# avocado-rev01_ODL.net
KiCad netlist of a schematic drawn in EAGLE
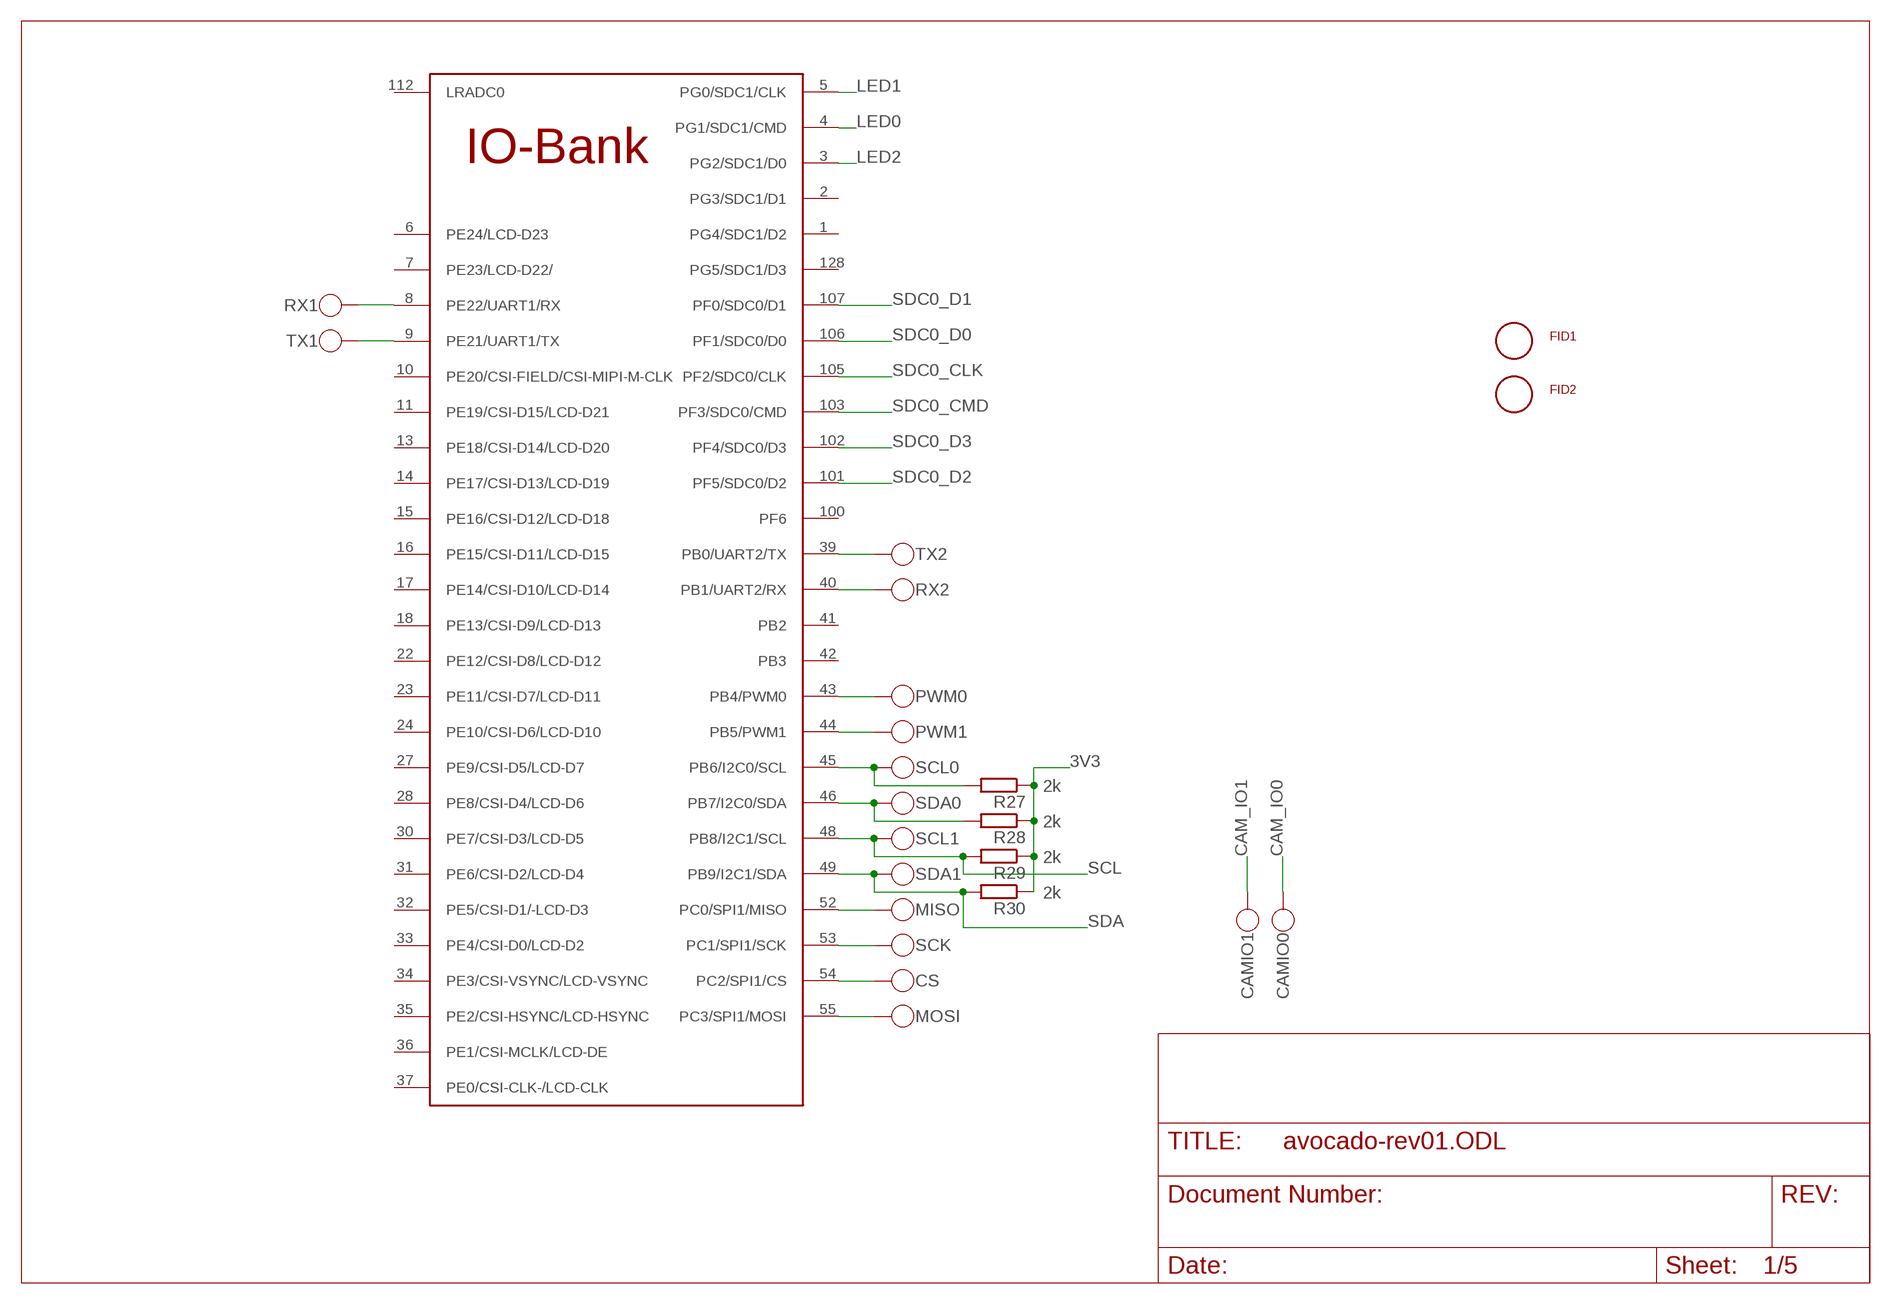
[diagram p0: schematic, sheet 1]
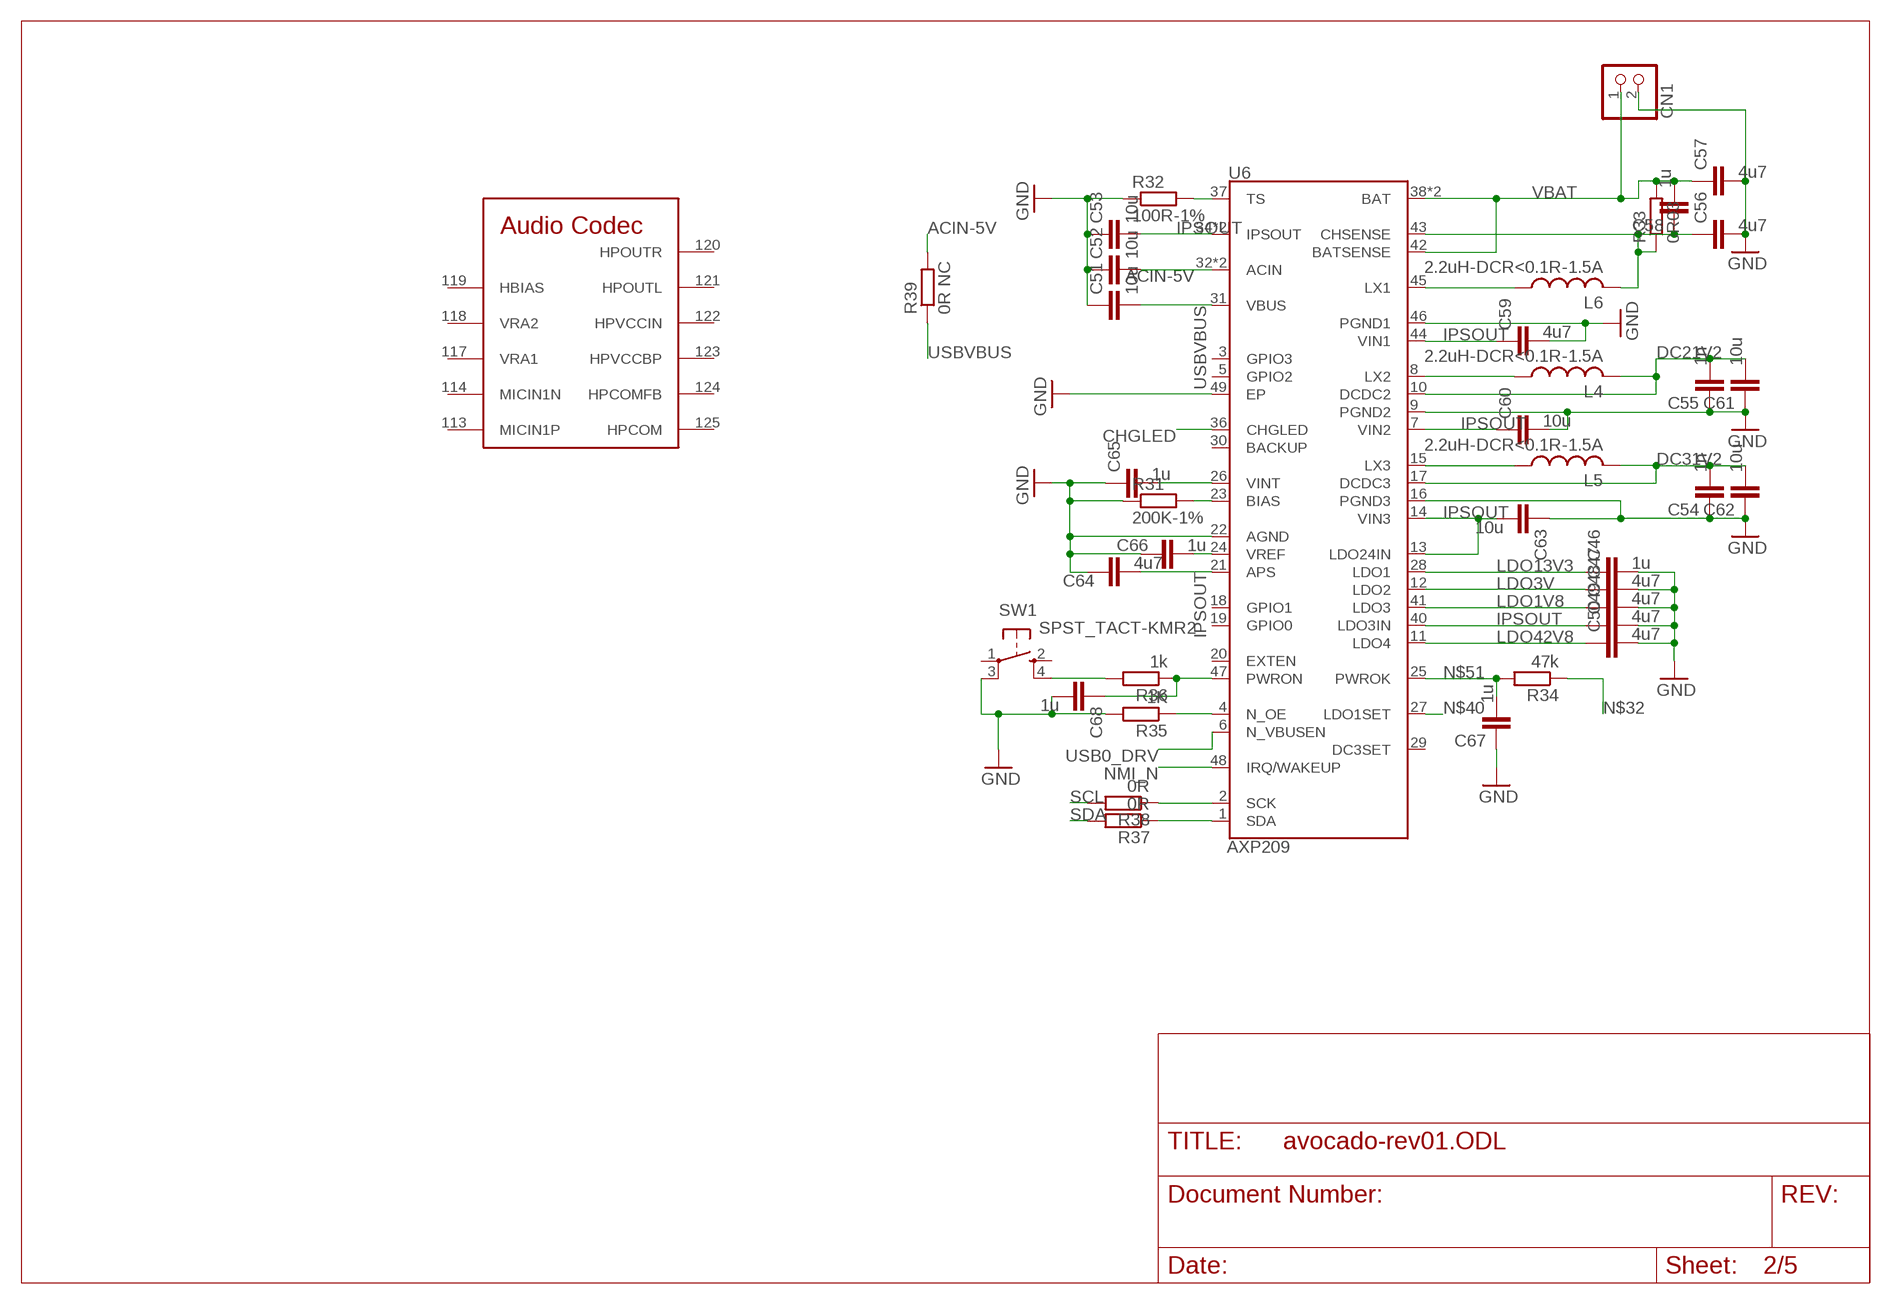
[diagram p1: schematic, sheet 2]
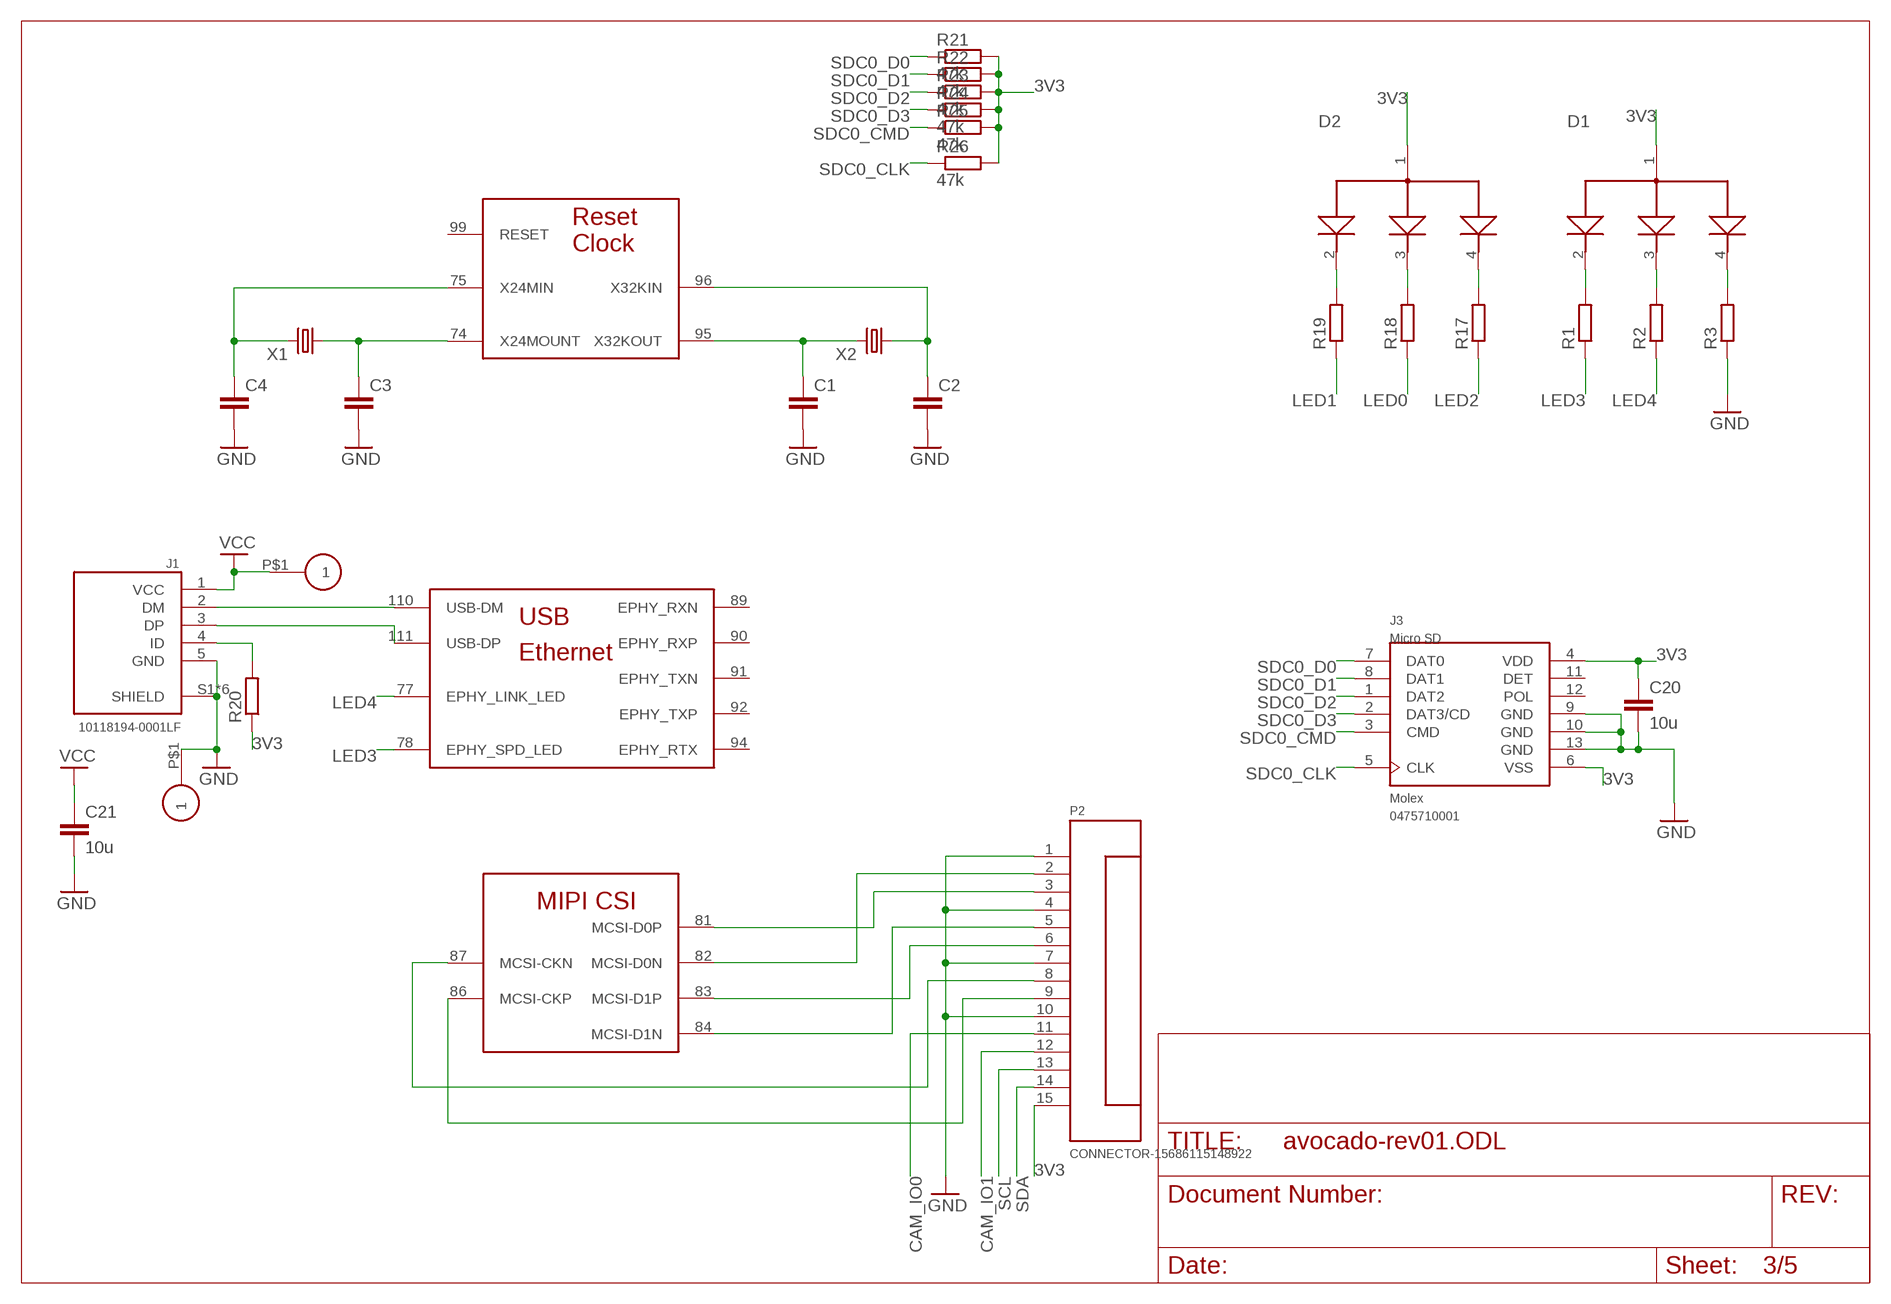
[diagram p2: schematic, sheet 3]
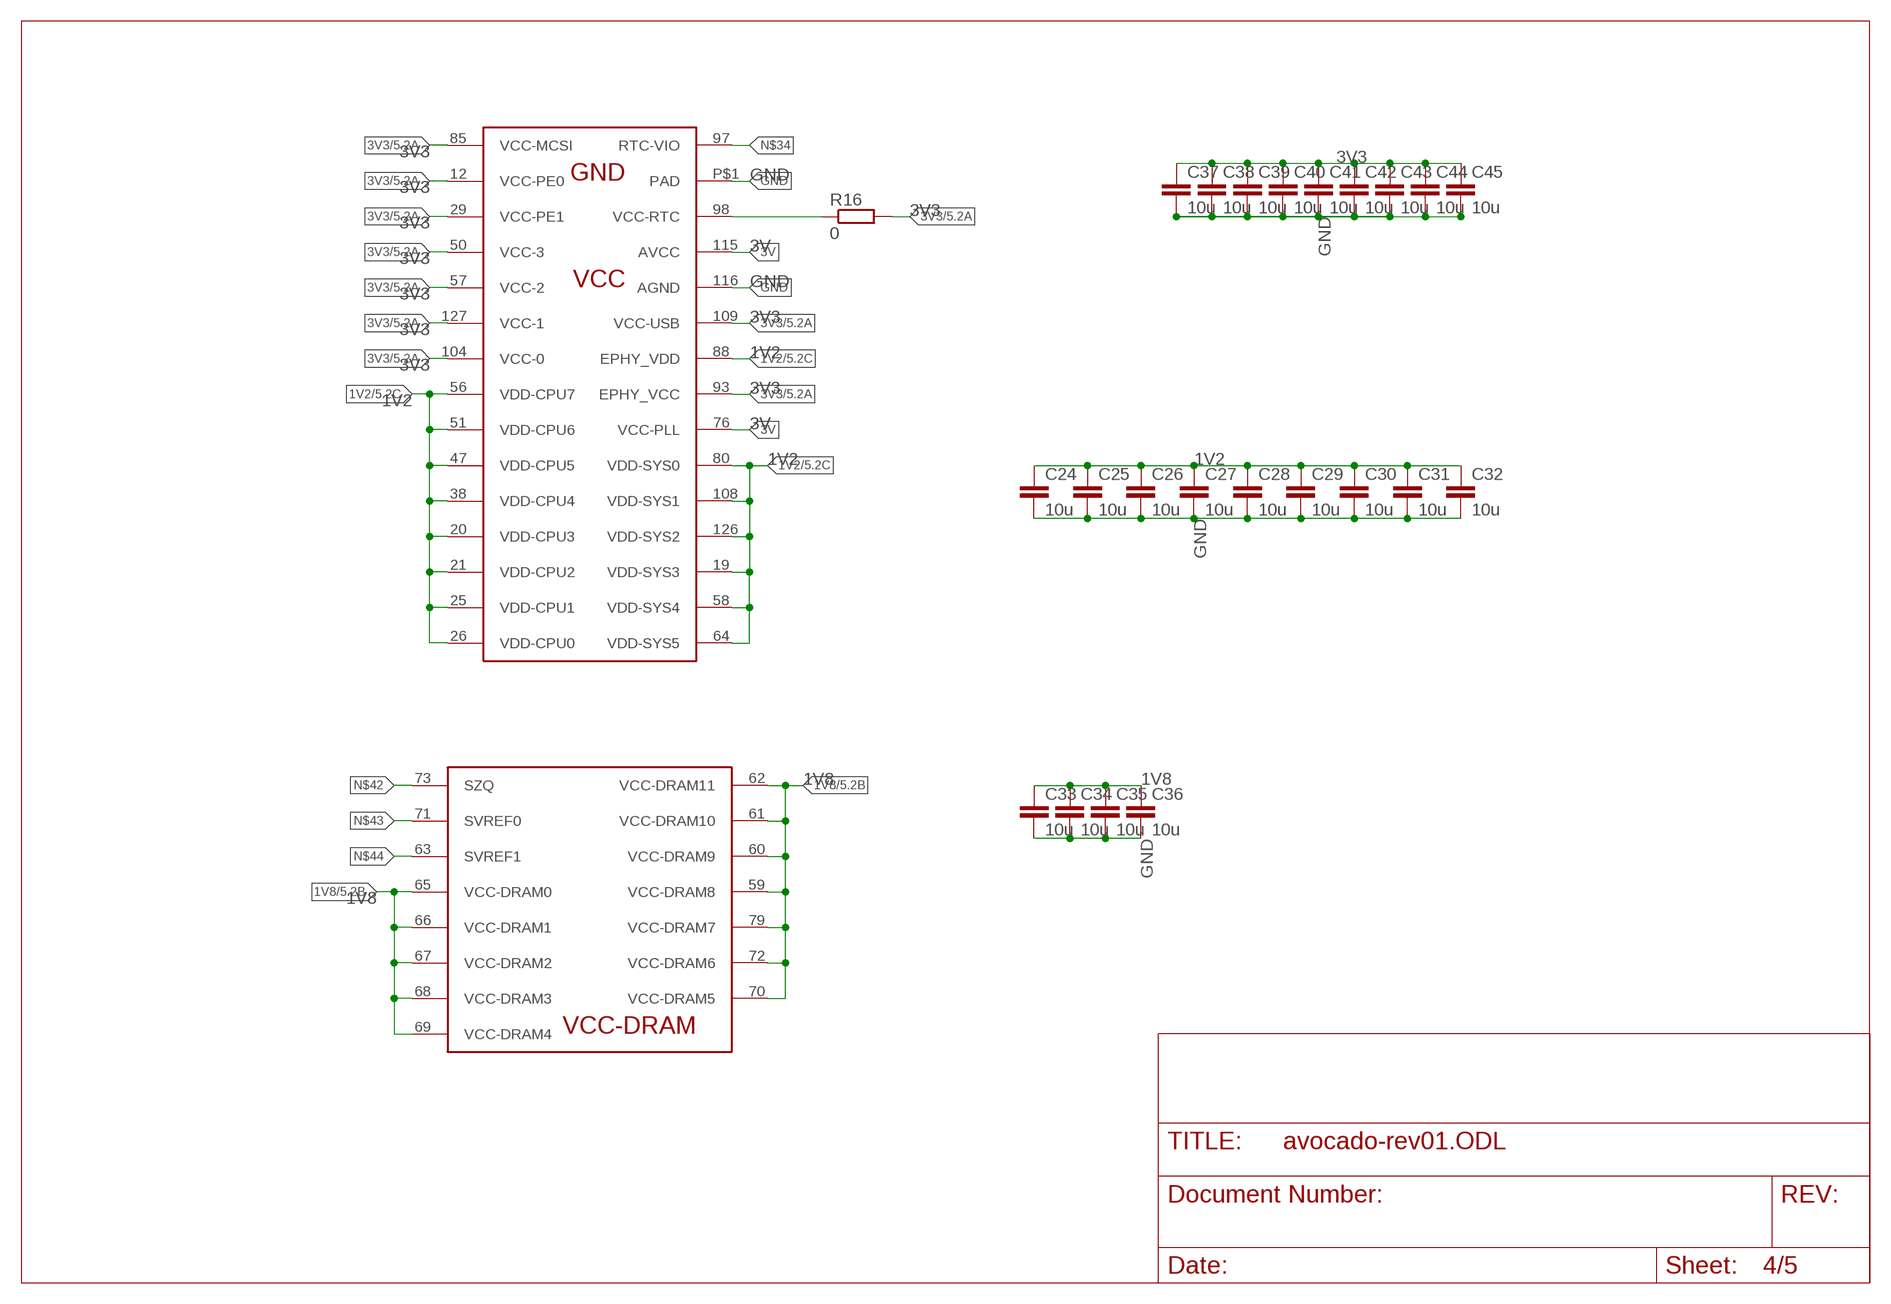
[diagram p3: schematic, sheet 4]
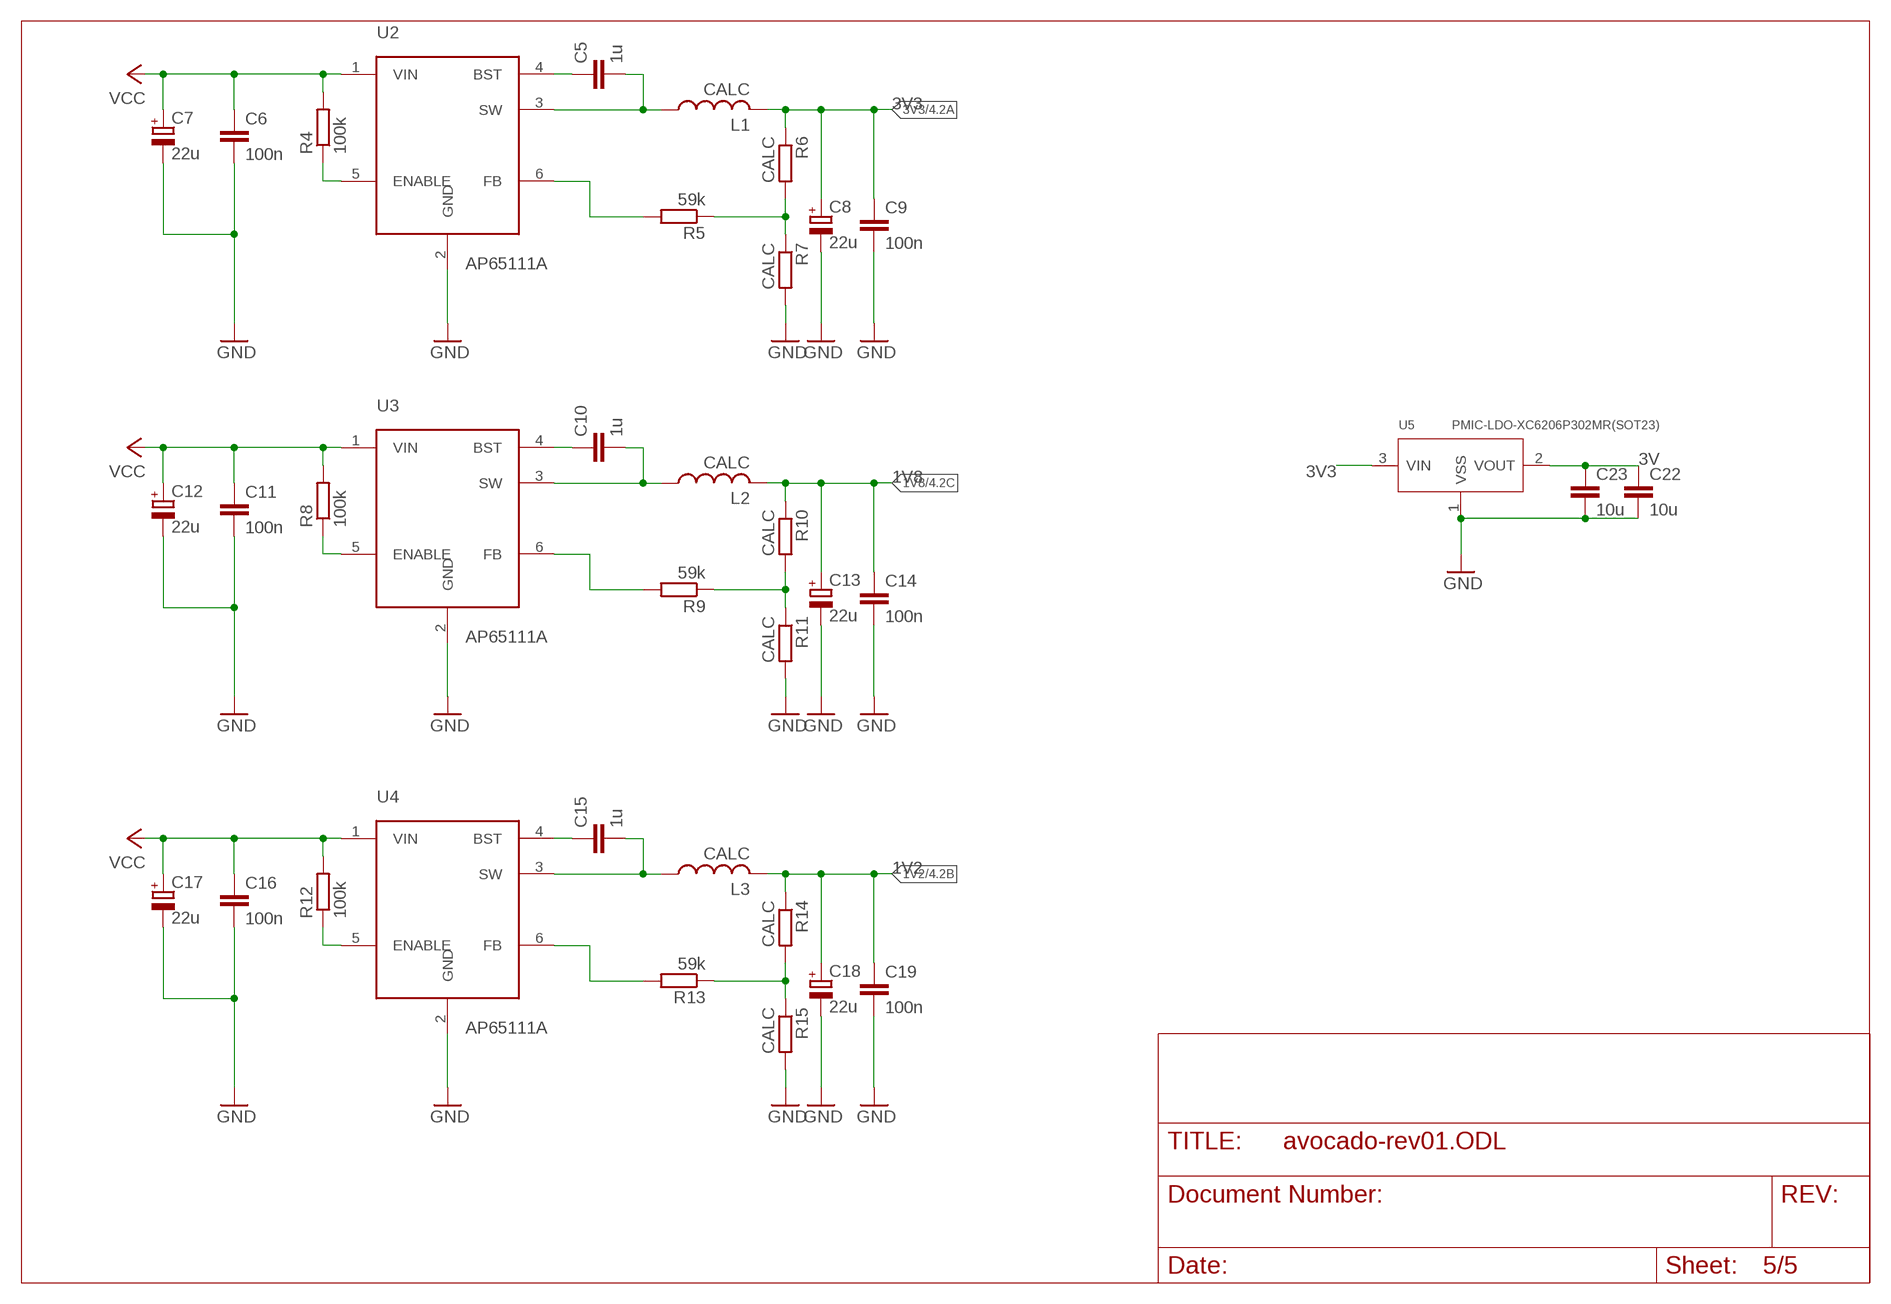
[diagram p4: schematic, sheet 5]

(export (version "E")
  (design (tool "Eeschema 10.0.6"))
  (components
    (comp (ref "C24")
      (value "10u")
      (footprint "eagle-import:C0603")
      (libsource (lib "eagle-import") (part "C0603"))
    )
    (comp (ref "C25")
      (value "10u")
      (footprint "eagle-import:C0603")
      (libsource (lib "eagle-import") (part "C0603"))
    )
    (comp (ref "C26")
      (value "10u")
      (footprint "eagle-import:C0603")
      (libsource (lib "eagle-import") (part "C0603"))
    )
    (comp (ref "C27")
      (value "10u")
      (footprint "eagle-import:C0603")
      (libsource (lib "eagle-import") (part "C0603"))
    )
    (comp (ref "C28")
      (value "10u")
      (footprint "eagle-import:C0603")
      (libsource (lib "eagle-import") (part "C0603"))
    )
    (comp (ref "C29")
      (value "10u")
      (footprint "eagle-import:C0603")
      (libsource (lib "eagle-import") (part "C0603"))
    )
    (comp (ref "C30")
      (value "10u")
      (footprint "eagle-import:C0603")
      (libsource (lib "eagle-import") (part "C0603"))
    )
    (comp (ref "C31")
      (value "10u")
      (footprint "eagle-import:C0603")
      (libsource (lib "eagle-import") (part "C0603"))
    )
    (comp (ref "C32")
      (value "10u")
      (footprint "eagle-import:C0603")
      (libsource (lib "eagle-import") (part "C0603"))
    )
    (comp (ref "C33")
      (value "10u")
      (footprint "eagle-import:C0603")
      (libsource (lib "eagle-import") (part "C0603"))
    )
    (comp (ref "C34")
      (value "10u")
      (footprint "eagle-import:C0603")
      (libsource (lib "eagle-import") (part "C0603"))
    )
    (comp (ref "C35")
      (value "10u")
      (footprint "eagle-import:C0603")
      (libsource (lib "eagle-import") (part "C0603"))
    )
    (comp (ref "C36")
      (value "10u")
      (footprint "eagle-import:C0603")
      (libsource (lib "eagle-import") (part "C0603"))
    )
    (comp (ref "C37")
      (value "10u")
      (footprint "eagle-import:C0603")
      (libsource (lib "eagle-import") (part "C0603"))
    )
    (comp (ref "C38")
      (value "10u")
      (footprint "eagle-import:C0603")
      (libsource (lib "eagle-import") (part "C0603"))
    )
    (comp (ref "C39")
      (value "10u")
      (footprint "eagle-import:C0603")
      (libsource (lib "eagle-import") (part "C0603"))
    )
    (comp (ref "C40")
      (value "10u")
      (footprint "eagle-import:C0603")
      (libsource (lib "eagle-import") (part "C0603"))
    )
    (comp (ref "C41")
      (value "10u")
      (footprint "eagle-import:C0603")
      (libsource (lib "eagle-import") (part "C0603"))
    )
    (comp (ref "C42")
      (value "10u")
      (footprint "eagle-import:C0603")
      (libsource (lib "eagle-import") (part "C0603"))
    )
    (comp (ref "C43")
      (value "10u")
      (footprint "eagle-import:C0603")
      (libsource (lib "eagle-import") (part "C0603"))
    )
    (comp (ref "C44")
      (value "10u")
      (footprint "eagle-import:C0603")
      (libsource (lib "eagle-import") (part "C0603"))
    )
    (comp (ref "C45")
      (value "10u")
      (footprint "eagle-import:C0603")
      (libsource (lib "eagle-import") (part "C0603"))
    )
    (comp (ref "R16")
      (value "0")
      (footprint "eagle-import:R0603")
      (libsource (lib "eagle-import") (part "R0603"))
    )
    (comp (ref "U1")
      (value "V3S")
      (footprint "eagle-import:QFP-128")
      (fields (field (name "MPN") "V3s"))
      (libsource (lib "eagle-import") (part "V3S"))
    )
    (comp (ref "C46")
      (value "1u")
      (footprint "eagle-import:C0603")
      (libsource (lib "eagle-import") (part "C0603"))
    )
    (comp (ref "C47")
      (value "4u7")
      (footprint "eagle-import:C0603")
      (libsource (lib "eagle-import") (part "C0603"))
    )
    (comp (ref "C48")
      (value "4u7")
      (footprint "eagle-import:C0603")
      (libsource (lib "eagle-import") (part "C0603"))
    )
    (comp (ref "C49")
      (value "4u7")
      (footprint "eagle-import:C0603")
      (libsource (lib "eagle-import") (part "C0603"))
    )
    (comp (ref "C50")
      (value "4u7")
      (footprint "eagle-import:C0603")
      (libsource (lib "eagle-import") (part "C0603"))
    )
    (comp (ref "C51")
      (value "10u")
      (footprint "eagle-import:C0603")
      (libsource (lib "eagle-import") (part "C0603"))
    )
    (comp (ref "C52")
      (value "10u")
      (footprint "eagle-import:C0603")
      (libsource (lib "eagle-import") (part "C0603"))
    )
    (comp (ref "C53")
      (value "10u")
      (footprint "eagle-import:C0603")
      (libsource (lib "eagle-import") (part "C0603"))
    )
    (comp (ref "C54")
      (value "1n")
      (footprint "eagle-import:C0603")
      (libsource (lib "eagle-import") (part "C0603"))
    )
    (comp (ref "C55")
      (value "1n")
      (footprint "eagle-import:C0603")
      (libsource (lib "eagle-import") (part "C0603"))
    )
    (comp (ref "C56")
      (value "4u7")
      (footprint "eagle-import:C0603")
      (libsource (lib "eagle-import") (part "C0603"))
    )
    (comp (ref "C57")
      (value "4u7")
      (footprint "eagle-import:C0603")
      (libsource (lib "eagle-import") (part "C0603"))
    )
    (comp (ref "C58")
      (value "1u")
      (footprint "eagle-import:C0603")
      (libsource (lib "eagle-import") (part "C0603"))
    )
    (comp (ref "C59")
      (value "4u7")
      (footprint "eagle-import:C0603")
      (libsource (lib "eagle-import") (part "C0603"))
    )
    (comp (ref "C60")
      (value "10u")
      (footprint "eagle-import:C0603")
      (libsource (lib "eagle-import") (part "C0603"))
    )
    (comp (ref "C61")
      (value "10u")
      (footprint "eagle-import:C0603")
      (libsource (lib "eagle-import") (part "C0603"))
    )
    (comp (ref "C62")
      (value "10u")
      (footprint "eagle-import:C0603")
      (libsource (lib "eagle-import") (part "C0603"))
    )
    (comp (ref "C63")
      (value "10u")
      (footprint "eagle-import:C0603")
      (libsource (lib "eagle-import") (part "C0603"))
    )
    (comp (ref "C64")
      (value "4u7")
      (footprint "eagle-import:C0603")
      (libsource (lib "eagle-import") (part "C0603"))
    )
    (comp (ref "C65")
      (value "1u")
      (footprint "eagle-import:C0603")
      (libsource (lib "eagle-import") (part "C0603"))
    )
    (comp (ref "C66")
      (value "1u")
      (footprint "eagle-import:C0603")
      (libsource (lib "eagle-import") (part "C0603"))
    )
    (comp (ref "C67")
      (value "1u")
      (footprint "eagle-import:C0603")
      (libsource (lib "eagle-import") (part "C0603"))
    )
    (comp (ref "C68")
      (value "1u")
      (footprint "eagle-import:C0603")
      (libsource (lib "eagle-import") (part "C0603"))
    )
    (comp (ref "CN1")
      (value "JST_2PIN-SMT-RA")
      (footprint "eagle-import:JST-PH-2-SMT-RA")
      (libsource (lib "eagle-import") (part "JST_2PIN-SMT-RA"))
    )
    (comp (ref "L4")
      (value "2.2uH-DCR<0.1R-1.5A")
      (footprint "eagle-import:B82462A4153K")
      (fields (field (name "MPN") "B82462A4153K"))
      (libsource (lib "eagle-import") (part "L6X6"))
    )
    (comp (ref "L5")
      (value "2.2uH-DCR<0.1R-1.5A")
      (footprint "eagle-import:B82462A4153K")
      (fields (field (name "MPN") "B82462A4153K"))
      (libsource (lib "eagle-import") (part "L6X6"))
    )
    (comp (ref "L6")
      (value "2.2uH-DCR<0.1R-1.5A")
      (footprint "eagle-import:B82462A4153K")
      (fields (field (name "MPN") "B82462A4153K"))
      (libsource (lib "eagle-import") (part "L6X6"))
    )
    (comp (ref "R31")
      (value "200K-1%")
      (footprint "eagle-import:R0402")
      (libsource (lib "eagle-import") (part "R-EU_R0402"))
    )
    (comp (ref "R32")
      (value "100R-1%")
      (footprint "eagle-import:R0402")
      (libsource (lib "eagle-import") (part "R-EU_R0402"))
    )
    (comp (ref "R33")
      (value "0R03")
      (footprint "eagle-import:R1206")
      (libsource (lib "eagle-import") (part "R-EU_R1206"))
    )
    (comp (ref "R34")
      (value "47k")
      (footprint "eagle-import:R0402")
      (libsource (lib "eagle-import") (part "R-EU_R0402"))
    )
    (comp (ref "R35")
      (value "1K")
      (footprint "eagle-import:R0402")
      (libsource (lib "eagle-import") (part "R-EU_R0402"))
    )
    (comp (ref "R36")
      (value "1k")
      (footprint "eagle-import:R0402")
      (libsource (lib "eagle-import") (part "R-EU_R0402"))
    )
    (comp (ref "R37")
      (value "0R")
      (footprint "eagle-import:R0402")
      (libsource (lib "eagle-import") (part "R-EU_R0402"))
    )
    (comp (ref "R38")
      (value "0R")
      (footprint "eagle-import:R0402")
      (libsource (lib "eagle-import") (part "R-EU_R0402"))
    )
    (comp (ref "R39")
      (value "0R NC")
      (footprint "eagle-import:R0402")
      (libsource (lib "eagle-import") (part "R-EU_R0402"))
    )
    (comp (ref "SW1")
      (value "SPST_TACT-KMR2")
      (footprint "eagle-import:KMR2")
      (libsource (lib "eagle-import") (part "SPST_TACT-KMR2"))
    )
    (comp (ref "U6")
      (value "AXP209")
      (footprint "eagle-import:QFN40P600X600X80-49N")
      (description "IC")
      (fields (field (name "MF") "X-Powers Limited"))
      (libsource (lib "eagle-import") (part "AXP209"))
    )
    (comp (ref "CAMIO0")
      (value "TEST_TESTPOINT")
      (footprint "eagle-import:TEST_TESTPOINT")
      (libsource (lib "eagle-import") (part "TEST_TESTPOINT"))
    )
    (comp (ref "CAMIO1")
      (value "TEST_TESTPOINT")
      (footprint "eagle-import:TEST_TESTPOINT")
      (libsource (lib "eagle-import") (part "TEST_TESTPOINT"))
    )
    (comp (ref "CS")
      (value "TEST_TESTPOINT")
      (footprint "eagle-import:TEST_TESTPOINT")
      (libsource (lib "eagle-import") (part "TEST_TESTPOINT"))
    )
    (comp (ref "FID1")
      (value "FIDUCIAL")
      (footprint "eagle-import:FIDUCIAL_1MM")
      (libsource (lib "eagle-import") (part "FIDUCIAL"))
    )
    (comp (ref "FID2")
      (value "FIDUCIAL")
      (footprint "eagle-import:FIDUCIAL_1MM")
      (libsource (lib "eagle-import") (part "FIDUCIAL"))
    )
    (comp (ref "MISO")
      (value "TEST_TESTPOINT")
      (footprint "eagle-import:TEST_TESTPOINT")
      (libsource (lib "eagle-import") (part "TEST_TESTPOINT"))
    )
    (comp (ref "MOSI")
      (value "TEST_TESTPOINT")
      (footprint "eagle-import:TEST_TESTPOINT")
      (libsource (lib "eagle-import") (part "TEST_TESTPOINT"))
    )
    (comp (ref "PWM0")
      (value "TEST_TESTPOINT")
      (footprint "eagle-import:TEST_TESTPOINT")
      (libsource (lib "eagle-import") (part "TEST_TESTPOINT"))
    )
    (comp (ref "PWM1")
      (value "TEST_TESTPOINT")
      (footprint "eagle-import:TEST_TESTPOINT")
      (libsource (lib "eagle-import") (part "TEST_TESTPOINT"))
    )
    (comp (ref "R27")
      (value "2k")
      (footprint "eagle-import:R0603")
      (libsource (lib "eagle-import") (part "R-EU_R0603"))
    )
    (comp (ref "R28")
      (value "2k")
      (footprint "eagle-import:R0603")
      (libsource (lib "eagle-import") (part "R-EU_R0603"))
    )
    (comp (ref "R29")
      (value "2k")
      (footprint "eagle-import:R0603")
      (libsource (lib "eagle-import") (part "R-EU_R0603"))
    )
    (comp (ref "R30")
      (value "2k")
      (footprint "eagle-import:R0603")
      (libsource (lib "eagle-import") (part "R-EU_R0603"))
    )
    (comp (ref "RX1")
      (value "TEST_TESTPOINT")
      (footprint "eagle-import:TEST_TESTPOINT")
      (libsource (lib "eagle-import") (part "TEST_TESTPOINT"))
    )
    (comp (ref "RX2")
      (value "TEST_TESTPOINT")
      (footprint "eagle-import:TEST_TESTPOINT")
      (libsource (lib "eagle-import") (part "TEST_TESTPOINT"))
    )
    (comp (ref "SCK")
      (value "TEST_TESTPOINT")
      (footprint "eagle-import:TEST_TESTPOINT")
      (libsource (lib "eagle-import") (part "TEST_TESTPOINT"))
    )
    (comp (ref "SCL0")
      (value "TEST_TESTPOINT")
      (footprint "eagle-import:TEST_TESTPOINT")
      (libsource (lib "eagle-import") (part "TEST_TESTPOINT"))
    )
    (comp (ref "SCL1")
      (value "TEST_TESTPOINT")
      (footprint "eagle-import:TEST_TESTPOINT")
      (libsource (lib "eagle-import") (part "TEST_TESTPOINT"))
    )
    (comp (ref "SDA0")
      (value "TEST_TESTPOINT")
      (footprint "eagle-import:TEST_TESTPOINT")
      (libsource (lib "eagle-import") (part "TEST_TESTPOINT"))
    )
    (comp (ref "SDA1")
      (value "TEST_TESTPOINT")
      (footprint "eagle-import:TEST_TESTPOINT")
      (libsource (lib "eagle-import") (part "TEST_TESTPOINT"))
    )
    (comp (ref "TX1")
      (value "TEST_TESTPOINT")
      (footprint "eagle-import:TEST_TESTPOINT")
      (libsource (lib "eagle-import") (part "TEST_TESTPOINT"))
    )
    (comp (ref "TX2")
      (value "TEST_TESTPOINT")
      (footprint "eagle-import:TEST_TESTPOINT")
      (libsource (lib "eagle-import") (part "TEST_TESTPOINT"))
    )
    (comp (ref "5V")
      (value "PADTH")
      (footprint "eagle-import:PAD")
      (libsource (lib "eagle-import") (part "PADTH"))
    )
    (comp (ref "C1")
      (value "C0603")
      (footprint "eagle-import:C0603")
      (libsource (lib "eagle-import") (part "C0603"))
    )
    (comp (ref "C2")
      (value "C0603")
      (footprint "eagle-import:C0603")
      (libsource (lib "eagle-import") (part "C0603"))
    )
    (comp (ref "C3")
      (value "C0603")
      (footprint "eagle-import:C0603")
      (libsource (lib "eagle-import") (part "C0603"))
    )
    (comp (ref "C4")
      (value "C0603")
      (footprint "eagle-import:C0603")
      (libsource (lib "eagle-import") (part "C0603"))
    )
    (comp (ref "C20")
      (value "10u")
      (footprint "eagle-import:C0603")
      (libsource (lib "eagle-import") (part "C0603"))
    )
    (comp (ref "C21")
      (value "10u")
      (footprint "eagle-import:C0603")
      (libsource (lib "eagle-import") (part "C0603"))
    )
    (comp (ref "D1")
      (value "LL-R3528RGBC-008-B")
      (footprint "eagle-import:LED_LL-R3528RGBC-008-B")
      (fields (field (name "MF") "Lucky Light"))
      (libsource (lib "eagle-import") (part "LL-R3528RGBC-008-B"))
    )
    (comp (ref "D2")
      (value "LL-R3528RGBC-008-B")
      (footprint "eagle-import:LED_LL-R3528RGBC-008-B")
      (fields (field (name "MF") "Lucky Light"))
      (libsource (lib "eagle-import") (part "LL-R3528RGBC-008-B"))
    )
    (comp (ref "GND")
      (value "PADTH")
      (footprint "eagle-import:PAD")
      (libsource (lib "eagle-import") (part "PADTH"))
    )
    (comp (ref "J1")
      (value "10118194-0001LF")
      (footprint "eagle-import:AMPHENOL_10118194-0001LF")
      (fields (field (name "MF") "Amphenol ICC"))
      (libsource (lib "eagle-import") (part "10118194-0001LF"))
    )
    (comp (ref "J3")
      (value "0475710001")
      (footprint "eagle-import:MOLEX_0475710001")
      (fields (field (name "MF") "Molex"))
      (libsource (lib "eagle-import") (part "0475710001"))
    )
    (comp (ref "P2")
      (value "CONNECTOR-15686115148922")
      (footprint "eagle-import:686115148922")
      (fields (field (name "MPN") "686115148922"))
      (libsource (lib "eagle-import") (part "CONNECTOR-15686115148922"))
    )
    (comp (ref "R1")
      (value "R-EU_R0603")
      (footprint "eagle-import:R0603")
      (libsource (lib "eagle-import") (part "R-EU_R0603"))
    )
    (comp (ref "R2")
      (value "R-EU_R0603")
      (footprint "eagle-import:R0603")
      (libsource (lib "eagle-import") (part "R-EU_R0603"))
    )
    (comp (ref "R3")
      (value "R-EU_R0603")
      (footprint "eagle-import:R0603")
      (libsource (lib "eagle-import") (part "R-EU_R0603"))
    )
    (comp (ref "R17")
      (value "R-EU_R0603")
      (footprint "eagle-import:R0603")
      (libsource (lib "eagle-import") (part "R-EU_R0603"))
    )
    (comp (ref "R18")
      (value "R-EU_R0603")
      (footprint "eagle-import:R0603")
      (libsource (lib "eagle-import") (part "R-EU_R0603"))
    )
    (comp (ref "R19")
      (value "R-EU_R0603")
      (footprint "eagle-import:R0603")
      (libsource (lib "eagle-import") (part "R-EU_R0603"))
    )
    (comp (ref "R20")
      (value "R-EU_R0603")
      (footprint "eagle-import:R0603")
      (libsource (lib "eagle-import") (part "R-EU_R0603"))
    )
    (comp (ref "R21")
      (value "47k")
      (footprint "eagle-import:R0603")
      (libsource (lib "eagle-import") (part "R-EU_R0603"))
    )
    (comp (ref "R22")
      (value "47k")
      (footprint "eagle-import:R0603")
      (libsource (lib "eagle-import") (part "R-EU_R0603"))
    )
    (comp (ref "R23")
      (value "47k")
      (footprint "eagle-import:R0603")
      (libsource (lib "eagle-import") (part "R-EU_R0603"))
    )
    (comp (ref "R24")
      (value "47k")
      (footprint "eagle-import:R0603")
      (libsource (lib "eagle-import") (part "R-EU_R0603"))
    )
    (comp (ref "R25")
      (value "47k")
      (footprint "eagle-import:R0603")
      (libsource (lib "eagle-import") (part "R-EU_R0603"))
    )
    (comp (ref "R26")
      (value "47k")
      (footprint "eagle-import:R0603")
      (libsource (lib "eagle-import") (part "R-EU_R0603"))
    )
    (comp (ref "X1")
      (value "XTAL3.2X2")
      (footprint "eagle-import:3.2X2-4")
      (libsource (lib "eagle-import") (part "XTAL3.2X2"))
    )
    (comp (ref "X2")
      (value "XTAL5X1.9")
      (footprint "eagle-import:XTAL-5X1.9")
      (libsource (lib "eagle-import") (part "XTAL5X1.9"))
    )
    (comp (ref "C5")
      (value "1u")
      (footprint "eagle-import:C0603")
      (libsource (lib "eagle-import") (part "C0603"))
    )
    (comp (ref "C6")
      (value "100n")
      (footprint "eagle-import:C0603")
      (libsource (lib "eagle-import") (part "C0603"))
    )
    (comp (ref "C7")
      (value "22u")
      (footprint "eagle-import:CAP4.3X6.1")
      (libsource (lib "eagle-import") (part "C_POL4.3"))
    )
    (comp (ref "C8")
      (value "22u")
      (footprint "eagle-import:CAP4.3X6.1")
      (libsource (lib "eagle-import") (part "C_POL4.3"))
    )
    (comp (ref "C9")
      (value "100n")
      (footprint "eagle-import:C0603")
      (libsource (lib "eagle-import") (part "C0603"))
    )
    (comp (ref "C10")
      (value "1u")
      (footprint "eagle-import:C0603")
      (libsource (lib "eagle-import") (part "C0603"))
    )
    (comp (ref "C11")
      (value "100n")
      (footprint "eagle-import:C0603")
      (libsource (lib "eagle-import") (part "C0603"))
    )
    (comp (ref "C12")
      (value "22u")
      (footprint "eagle-import:CAP4.3X6.1")
      (libsource (lib "eagle-import") (part "C_POL4.3"))
    )
    (comp (ref "C13")
      (value "22u")
      (footprint "eagle-import:CAP4.3X6.1")
      (libsource (lib "eagle-import") (part "C_POL4.3"))
    )
    (comp (ref "C14")
      (value "100n")
      (footprint "eagle-import:C0603")
      (libsource (lib "eagle-import") (part "C0603"))
    )
    (comp (ref "C15")
      (value "1u")
      (footprint "eagle-import:C0603")
      (libsource (lib "eagle-import") (part "C0603"))
    )
    (comp (ref "C16")
      (value "100n")
      (footprint "eagle-import:C0603")
      (libsource (lib "eagle-import") (part "C0603"))
    )
    (comp (ref "C17")
      (value "22u")
      (footprint "eagle-import:CAP4.3X6.1")
      (libsource (lib "eagle-import") (part "C_POL4.3"))
    )
    (comp (ref "C18")
      (value "22u")
      (footprint "eagle-import:CAP4.3X6.1")
      (libsource (lib "eagle-import") (part "C_POL4.3"))
    )
    (comp (ref "C19")
      (value "100n")
      (footprint "eagle-import:C0603")
      (libsource (lib "eagle-import") (part "C0603"))
    )
    (comp (ref "C22")
      (value "10u")
      (footprint "eagle-import:C0603")
      (libsource (lib "eagle-import") (part "C0603"))
    )
    (comp (ref "C23")
      (value "10u")
      (footprint "eagle-import:C0603")
      (libsource (lib "eagle-import") (part "C0603"))
    )
    (comp (ref "L1")
      (value "CALC")
      (footprint "eagle-import:B82462A4153K")
      (fields (field (name "MPN") "B82462A4153K"))
      (libsource (lib "eagle-import") (part "L6X6"))
    )
    (comp (ref "L2")
      (value "CALC")
      (footprint "eagle-import:B82462A4153K")
      (fields (field (name "MPN") "B82462A4153K"))
      (libsource (lib "eagle-import") (part "L6X6"))
    )
    (comp (ref "L3")
      (value "CALC")
      (footprint "eagle-import:B82462A4153K")
      (fields (field (name "MPN") "B82462A4153K"))
      (libsource (lib "eagle-import") (part "L6X6"))
    )
    (comp (ref "R4")
      (value "100k")
      (footprint "eagle-import:R0603")
      (libsource (lib "eagle-import") (part "R0603"))
    )
    (comp (ref "R5")
      (value "59k")
      (footprint "eagle-import:R0603")
      (libsource (lib "eagle-import") (part "R0603"))
    )
    (comp (ref "R6")
      (value "CALC")
      (footprint "eagle-import:R0603")
      (libsource (lib "eagle-import") (part "R0603"))
    )
    (comp (ref "R7")
      (value "CALC")
      (footprint "eagle-import:R0603")
      (libsource (lib "eagle-import") (part "R0603"))
    )
    (comp (ref "R8")
      (value "100k")
      (footprint "eagle-import:R0603")
      (libsource (lib "eagle-import") (part "R0603"))
    )
    (comp (ref "R9")
      (value "59k")
      (footprint "eagle-import:R0603")
      (libsource (lib "eagle-import") (part "R0603"))
    )
    (comp (ref "R10")
      (value "CALC")
      (footprint "eagle-import:R0603")
      (libsource (lib "eagle-import") (part "R0603"))
    )
    (comp (ref "R11")
      (value "CALC")
      (footprint "eagle-import:R0603")
      (libsource (lib "eagle-import") (part "R0603"))
    )
    (comp (ref "R12")
      (value "100k")
      (footprint "eagle-import:R0603")
      (libsource (lib "eagle-import") (part "R0603"))
    )
    (comp (ref "R13")
      (value "59k")
      (footprint "eagle-import:R0603")
      (libsource (lib "eagle-import") (part "R0603"))
    )
    (comp (ref "R14")
      (value "CALC")
      (footprint "eagle-import:R0603")
      (libsource (lib "eagle-import") (part "R0603"))
    )
    (comp (ref "R15")
      (value "CALC")
      (footprint "eagle-import:R0603")
      (libsource (lib "eagle-import") (part "R0603"))
    )
    (comp (ref "U2")
      (value "AP65111A")
      (footprint "eagle-import:TSOT26")
      (fields (field (name "MPN") "AP65111AWU-7"))
      (libsource (lib "eagle-import") (part "AP65111A"))
    )
    (comp (ref "U3")
      (value "AP65111A")
      (footprint "eagle-import:TSOT26")
      (fields (field (name "MPN") "AP65111AWU-7"))
      (libsource (lib "eagle-import") (part "AP65111A"))
    )
    (comp (ref "U4")
      (value "AP65111A")
      (footprint "eagle-import:TSOT26")
      (fields (field (name "MPN") "AP65111AWU-7"))
      (libsource (lib "eagle-import") (part "AP65111A"))
    )
    (comp (ref "U5")
      (value "PMIC-LDO-XC6206P302MR(SOT23)")
      (footprint "eagle-import:SOT-23")
      (description "N/A")
      (fields
        (field (name "MF") "Torex")
        (field (name "MP") "XC6206P302MR")
        (field (name "AVAILABILITY") "N/A")
      )
      (libsource (lib "eagle-import") (part "PMIC-LDO-XC6206P302MR(SOT23)"))
    )
  )
  (nets
    (net (code "1") (name "1V2") (class "Default")
      (node (ref "C18") (pin "1") (pinfunction "+_1") (pintype "passive"))
      (node (ref "C19") (pin "1") (pinfunction "1_1") (pintype "passive"))
      (node (ref "C24") (pin "1") (pinfunction "1_1") (pintype "passive"))
      (node (ref "C25") (pin "1") (pinfunction "1_1") (pintype "passive"))
      (node (ref "C26") (pin "1") (pinfunction "1_1") (pintype "passive"))
      (node (ref "C27") (pin "1") (pinfunction "1_1") (pintype "passive"))
      (node (ref "C28") (pin "1") (pinfunction "1_1") (pintype "passive"))
      (node (ref "C29") (pin "1") (pinfunction "1_1") (pintype "passive"))
      (node (ref "C30") (pin "1") (pinfunction "1_1") (pintype "passive"))
      (node (ref "C31") (pin "1") (pinfunction "1_1") (pintype "passive"))
      (node (ref "C32") (pin "1") (pinfunction "1_1") (pintype "passive"))
      (node (ref "L3") (pin "P$2") (pinfunction "2_P$2") (pintype "passive"))
      (node (ref "R14") (pin "1") (pinfunction "1_1") (pintype "passive"))
      (node (ref "U1") (pin "108") (pinfunction "VDD-SYS1_108") (pintype "bidirectional"))
      (node (ref "U1") (pin "126") (pinfunction "VDD-SYS2_126") (pintype "bidirectional"))
      (node (ref "U1") (pin "19") (pinfunction "VDD-SYS3_19") (pintype "bidirectional"))
      (node (ref "U1") (pin "20") (pinfunction "VDD-CPU3_20") (pintype "bidirectional"))
      (node (ref "U1") (pin "21") (pinfunction "VDD-CPU2_21") (pintype "bidirectional"))
      (node (ref "U1") (pin "25") (pinfunction "VDD-CPU1_25") (pintype "bidirectional"))
      (node (ref "U1") (pin "26") (pinfunction "VDD-CPU0_26") (pintype "bidirectional"))
      (node (ref "U1") (pin "38") (pinfunction "VDD-CPU4_38") (pintype "bidirectional"))
      (node (ref "U1") (pin "47") (pinfunction "VDD-CPU5_47") (pintype "bidirectional"))
      (node (ref "U1") (pin "51") (pinfunction "VDD-CPU6_51") (pintype "bidirectional"))
      (node (ref "U1") (pin "56") (pinfunction "VDD-CPU7_56") (pintype "bidirectional"))
      (node (ref "U1") (pin "58") (pinfunction "VDD-SYS4_58") (pintype "bidirectional"))
      (node (ref "U1") (pin "64") (pinfunction "VDD-SYS5_64") (pintype "bidirectional"))
      (node (ref "U1") (pin "80") (pinfunction "VDD-SYS0_80") (pintype "bidirectional"))
      (node (ref "U1") (pin "88") (pinfunction "EPHY_VDD_88") (pintype "bidirectional"))
    )
    (net (code "2") (name "1V8") (class "Default")
      (node (ref "C13") (pin "1") (pinfunction "+_1") (pintype "passive"))
      (node (ref "C14") (pin "1") (pinfunction "1_1") (pintype "passive"))
      (node (ref "C33") (pin "1") (pinfunction "1_1") (pintype "passive"))
      (node (ref "C34") (pin "1") (pinfunction "1_1") (pintype "passive"))
      (node (ref "C35") (pin "1") (pinfunction "1_1") (pintype "passive"))
      (node (ref "C36") (pin "1") (pinfunction "1_1") (pintype "passive"))
      (node (ref "L2") (pin "P$2") (pinfunction "2_P$2") (pintype "passive"))
      (node (ref "R10") (pin "1") (pinfunction "1_1") (pintype "passive"))
      (node (ref "U1") (pin "59") (pinfunction "VCC-DRAM8_59") (pintype "bidirectional"))
      (node (ref "U1") (pin "60") (pinfunction "VCC-DRAM9_60") (pintype "bidirectional"))
      (node (ref "U1") (pin "61") (pinfunction "VCC-DRAM10_61") (pintype "bidirectional"))
      (node (ref "U1") (pin "62") (pinfunction "VCC-DRAM11_62") (pintype "bidirectional"))
      (node (ref "U1") (pin "65") (pinfunction "VCC-DRAM0_65") (pintype "bidirectional"))
      (node (ref "U1") (pin "66") (pinfunction "VCC-DRAM1_66") (pintype "bidirectional"))
      (node (ref "U1") (pin "67") (pinfunction "VCC-DRAM2_67") (pintype "bidirectional"))
      (node (ref "U1") (pin "68") (pinfunction "VCC-DRAM3_68") (pintype "bidirectional"))
      (node (ref "U1") (pin "69") (pinfunction "VCC-DRAM4_69") (pintype "bidirectional"))
      (node (ref "U1") (pin "70") (pinfunction "VCC-DRAM5_70") (pintype "bidirectional"))
      (node (ref "U1") (pin "72") (pinfunction "VCC-DRAM6_72") (pintype "bidirectional"))
      (node (ref "U1") (pin "79") (pinfunction "VCC-DRAM7_79") (pintype "bidirectional"))
    )
    (net (code "3") (name "3V") (class "Default")
      (node (ref "C22") (pin "1") (pinfunction "1_1") (pintype "passive"))
      (node (ref "C23") (pin "1") (pinfunction "1_1") (pintype "passive"))
      (node (ref "U1") (pin "115") (pinfunction "AVCC_115") (pintype "bidirectional"))
      (node (ref "U1") (pin "76") (pinfunction "VCC-PLL_76") (pintype "bidirectional"))
      (node (ref "U5") (pin "2") (pinfunction "VOUT_2") (pintype "output"))
    )
    (net (code "4") (name "3V3") (class "Default")
      (node (ref "C20") (pin "1") (pinfunction "1_1") (pintype "passive"))
      (node (ref "C37") (pin "1") (pinfunction "1_1") (pintype "passive"))
      (node (ref "C38") (pin "1") (pinfunction "1_1") (pintype "passive"))
      (node (ref "C39") (pin "1") (pinfunction "1_1") (pintype "passive"))
      (node (ref "C40") (pin "1") (pinfunction "1_1") (pintype "passive"))
      (node (ref "C41") (pin "1") (pinfunction "1_1") (pintype "passive"))
      (node (ref "C42") (pin "1") (pinfunction "1_1") (pintype "passive"))
      (node (ref "C43") (pin "1") (pinfunction "1_1") (pintype "passive"))
      (node (ref "C44") (pin "1") (pinfunction "1_1") (pintype "passive"))
      (node (ref "C45") (pin "1") (pinfunction "1_1") (pintype "passive"))
      (node (ref "C8") (pin "1") (pinfunction "+_1") (pintype "passive"))
      (node (ref "C9") (pin "1") (pinfunction "1_1") (pintype "passive"))
      (node (ref "D1") (pin "1") (pinfunction "COMM_ANODE_1") (pintype "passive"))
      (node (ref "D2") (pin "1") (pinfunction "COMM_ANODE_1") (pintype "passive"))
      (node (ref "J3") (pin "4") (pinfunction "VDD_4") (pintype "power_in"))
      (node (ref "J3") (pin "6") (pinfunction "VSS_6") (pintype "power_in"))
      (node (ref "L1") (pin "P$2") (pinfunction "2_P$2") (pintype "passive"))
      (node (ref "P2") (pin "15") (pinfunction "15_15") (pintype "bidirectional"))
      (node (ref "R16") (pin "2") (pinfunction "2_2") (pintype "passive"))
      (node (ref "R20") (pin "1") (pinfunction "1_1") (pintype "passive"))
      (node (ref "R21") (pin "2") (pinfunction "2_2") (pintype "passive"))
      (node (ref "R22") (pin "2") (pinfunction "2_2") (pintype "passive"))
      (node (ref "R23") (pin "2") (pinfunction "2_2") (pintype "passive"))
      (node (ref "R24") (pin "2") (pinfunction "2_2") (pintype "passive"))
      (node (ref "R25") (pin "2") (pinfunction "2_2") (pintype "passive"))
      (node (ref "R26") (pin "2") (pinfunction "2_2") (pintype "passive"))
      (node (ref "R27") (pin "1") (pinfunction "1_1") (pintype "passive"))
      (node (ref "R28") (pin "1") (pinfunction "1_1") (pintype "passive"))
      (node (ref "R29") (pin "1") (pinfunction "1_1") (pintype "passive"))
      (node (ref "R30") (pin "1") (pinfunction "1_1") (pintype "passive"))
      (node (ref "R6") (pin "1") (pinfunction "1_1") (pintype "passive"))
      (node (ref "U1") (pin "104") (pinfunction "VCC-0_104") (pintype "bidirectional"))
      (node (ref "U1") (pin "109") (pinfunction "VCC-USB_109") (pintype "bidirectional"))
      (node (ref "U1") (pin "12") (pinfunction "VCC-PE0_12") (pintype "bidirectional"))
      (node (ref "U1") (pin "127") (pinfunction "VCC-1_127") (pintype "bidirectional"))
      (node (ref "U1") (pin "29") (pinfunction "VCC-PE1_29") (pintype "bidirectional"))
      (node (ref "U1") (pin "50") (pinfunction "VCC-3_50") (pintype "bidirectional"))
      (node (ref "U1") (pin "57") (pinfunction "VCC-2_57") (pintype "bidirectional"))
      (node (ref "U1") (pin "85") (pinfunction "VCC-MCSI_85") (pintype "bidirectional"))
      (node (ref "U1") (pin "93") (pinfunction "EPHY_VCC_93") (pintype "bidirectional"))
      (node (ref "U5") (pin "3") (pinfunction "VIN_3") (pintype "input"))
    )
    (net (code "5") (name "ACIN-5V") (class "Default")
      (node (ref "C52") (pin "2") (pinfunction "2_2") (pintype "passive"))
      (node (ref "R39") (pin "2") (pinfunction "2_2") (pintype "passive"))
      (node (ref "U6") (pin "32") (pinfunction "ACIN_32") (pintype "power_in"))
      (node (ref "U6") (pin "33") (pinfunction "ACIN_33") (pintype "power_in"))
    )
    (net (code "6") (name "CAM_IO0") (class "Default")
      (node (ref "CAMIO0") (pin "1") (pinfunction "2_1") (pintype "passive"))
      (node (ref "P2") (pin "11") (pinfunction "11_11") (pintype "bidirectional"))
    )
    (net (code "7") (name "CAM_IO1") (class "Default")
      (node (ref "CAMIO1") (pin "1") (pinfunction "2_1") (pintype "passive"))
      (node (ref "P2") (pin "12") (pinfunction "12_12") (pintype "bidirectional"))
    )
    (net (code "8") (name "CHGLED") (class "Default")
      (node (ref "U6") (pin "36") (pinfunction "CHGLED_36") (pintype "output"))
    )
    (net (code "9") (name "DC21V2") (class "Default")
      (node (ref "C55") (pin "2") (pinfunction "2_2") (pintype "passive"))
      (node (ref "C61") (pin "2") (pinfunction "2_2") (pintype "passive"))
      (node (ref "L4") (pin "P$2") (pinfunction "2_P$2") (pintype "passive"))
      (node (ref "U6") (pin "10") (pinfunction "DCDC2_10") (pintype "input"))
    )
    (net (code "10") (name "DC31V2") (class "Default")
      (node (ref "C54") (pin "2") (pinfunction "2_2") (pintype "passive"))
      (node (ref "C62") (pin "2") (pinfunction "2_2") (pintype "passive"))
      (node (ref "L5") (pin "P$2") (pinfunction "2_P$2") (pintype "passive"))
      (node (ref "U6") (pin "17") (pinfunction "DCDC3_17") (pintype "input"))
    )
    (net (code "11") (name "GND") (class "Default")
      (node (ref "C1") (pin "2") (pinfunction "2_2") (pintype "passive"))
      (node (ref "C11") (pin "2") (pinfunction "2_2") (pintype "passive"))
      (node (ref "C12") (pin "2") (pinfunction "-_2") (pintype "passive"))
      (node (ref "C13") (pin "2") (pinfunction "-_2") (pintype "passive"))
      (node (ref "C14") (pin "2") (pinfunction "2_2") (pintype "passive"))
      (node (ref "C16") (pin "2") (pinfunction "2_2") (pintype "passive"))
      (node (ref "C17") (pin "2") (pinfunction "-_2") (pintype "passive"))
      (node (ref "C18") (pin "2") (pinfunction "-_2") (pintype "passive"))
      (node (ref "C19") (pin "2") (pinfunction "2_2") (pintype "passive"))
      (node (ref "C2") (pin "2") (pinfunction "2_2") (pintype "passive"))
      (node (ref "C20") (pin "2") (pinfunction "2_2") (pintype "passive"))
      (node (ref "C21") (pin "2") (pinfunction "2_2") (pintype "passive"))
      (node (ref "C22") (pin "2") (pinfunction "2_2") (pintype "passive"))
      (node (ref "C23") (pin "2") (pinfunction "2_2") (pintype "passive"))
      (node (ref "C24") (pin "2") (pinfunction "2_2") (pintype "passive"))
      (node (ref "C25") (pin "2") (pinfunction "2_2") (pintype "passive"))
      (node (ref "C26") (pin "2") (pinfunction "2_2") (pintype "passive"))
      (node (ref "C27") (pin "2") (pinfunction "2_2") (pintype "passive"))
      (node (ref "C28") (pin "2") (pinfunction "2_2") (pintype "passive"))
      (node (ref "C29") (pin "2") (pinfunction "2_2") (pintype "passive"))
      (node (ref "C3") (pin "2") (pinfunction "2_2") (pintype "passive"))
      (node (ref "C30") (pin "2") (pinfunction "2_2") (pintype "passive"))
      (node (ref "C31") (pin "2") (pinfunction "2_2") (pintype "passive"))
      (node (ref "C32") (pin "2") (pinfunction "2_2") (pintype "passive"))
      (node (ref "C33") (pin "2") (pinfunction "2_2") (pintype "passive"))
      (node (ref "C34") (pin "2") (pinfunction "2_2") (pintype "passive"))
      (node (ref "C35") (pin "2") (pinfunction "2_2") (pintype "passive"))
      (node (ref "C36") (pin "2") (pinfunction "2_2") (pintype "passive"))
      (node (ref "C37") (pin "2") (pinfunction "2_2") (pintype "passive"))
      (node (ref "C38") (pin "2") (pinfunction "2_2") (pintype "passive"))
      (node (ref "C39") (pin "2") (pinfunction "2_2") (pintype "passive"))
      (node (ref "C4") (pin "2") (pinfunction "2_2") (pintype "passive"))
      (node (ref "C40") (pin "2") (pinfunction "2_2") (pintype "passive"))
      (node (ref "C41") (pin "2") (pinfunction "2_2") (pintype "passive"))
      (node (ref "C42") (pin "2") (pinfunction "2_2") (pintype "passive"))
      (node (ref "C43") (pin "2") (pinfunction "2_2") (pintype "passive"))
      (node (ref "C44") (pin "2") (pinfunction "2_2") (pintype "passive"))
      (node (ref "C45") (pin "2") (pinfunction "2_2") (pintype "passive"))
      (node (ref "C46") (pin "2") (pinfunction "2_2") (pintype "passive"))
      (node (ref "C47") (pin "2") (pinfunction "2_2") (pintype "passive"))
      (node (ref "C48") (pin "2") (pinfunction "2_2") (pintype "passive"))
      (node (ref "C49") (pin "2") (pinfunction "2_2") (pintype "passive"))
      (node (ref "C50") (pin "2") (pinfunction "2_2") (pintype "passive"))
      (node (ref "C51") (pin "1") (pinfunction "1_1") (pintype "passive"))
      (node (ref "C52") (pin "1") (pinfunction "1_1") (pintype "passive"))
      (node (ref "C53") (pin "1") (pinfunction "1_1") (pintype "passive"))
      (node (ref "C54") (pin "1") (pinfunction "1_1") (pintype "passive"))
      (node (ref "C55") (pin "1") (pinfunction "1_1") (pintype "passive"))
      (node (ref "C56") (pin "2") (pinfunction "2_2") (pintype "passive"))
      (node (ref "C57") (pin "2") (pinfunction "2_2") (pintype "passive"))
      (node (ref "C59") (pin "2") (pinfunction "2_2") (pintype "passive"))
      (node (ref "C6") (pin "2") (pinfunction "2_2") (pintype "passive"))
      (node (ref "C60") (pin "2") (pinfunction "2_2") (pintype "passive"))
      (node (ref "C61") (pin "1") (pinfunction "1_1") (pintype "passive"))
      (node (ref "C62") (pin "1") (pinfunction "1_1") (pintype "passive"))
      (node (ref "C63") (pin "1") (pinfunction "1_1") (pintype "passive"))
      (node (ref "C64") (pin "1") (pinfunction "1_1") (pintype "passive"))
      (node (ref "C65") (pin "1") (pinfunction "1_1") (pintype "passive"))
      (node (ref "C66") (pin "1") (pinfunction "1_1") (pintype "passive"))
      (node (ref "C67") (pin "1") (pinfunction "1_1") (pintype "passive"))
      (node (ref "C68") (pin "2") (pinfunction "2_2") (pintype "passive"))
      (node (ref "C7") (pin "2") (pinfunction "-_2") (pintype "passive"))
      (node (ref "C8") (pin "2") (pinfunction "-_2") (pintype "passive"))
      (node (ref "C9") (pin "2") (pinfunction "2_2") (pintype "passive"))
      (node (ref "CN1") (pin "2") (pinfunction "1_2") (pintype "passive"))
      (node (ref "GND") (pin "P$1") (pinfunction "1_P$1") (pintype "bidirectional"))
      (node (ref "J1") (pin "5") (pinfunction "GND_5") (pintype "passive"))
      (node (ref "J1") (pin "S1") (pinfunction "SHIELD_S1") (pintype "passive"))
      (node (ref "J1") (pin "S2") (pinfunction "SHIELD_S2") (pintype "passive"))
      (node (ref "J1") (pin "S3") (pinfunction "SHIELD_S3") (pintype "passive"))
      (node (ref "J1") (pin "S4") (pinfunction "SHIELD_S4") (pintype "passive"))
      (node (ref "J1") (pin "S5") (pinfunction "SHIELD_S5") (pintype "passive"))
      (node (ref "J1") (pin "S6") (pinfunction "SHIELD_S6") (pintype "passive"))
      (node (ref "J3") (pin "10") (pinfunction "GND_10") (pintype "power_in"))
      (node (ref "J3") (pin "13") (pinfunction "GND_13") (pintype "power_in"))
      (node (ref "J3") (pin "9") (pinfunction "GND_9") (pintype "power_in"))
      (node (ref "P2") (pin "1") (pinfunction "1_1") (pintype "bidirectional"))
      (node (ref "P2") (pin "10") (pinfunction "10_10") (pintype "bidirectional"))
      (node (ref "P2") (pin "4") (pinfunction "4_4") (pintype "bidirectional"))
      (node (ref "P2") (pin "7") (pinfunction "7_7") (pintype "bidirectional"))
      (node (ref "R11") (pin "2") (pinfunction "2_2") (pintype "passive"))
      (node (ref "R15") (pin "2") (pinfunction "2_2") (pintype "passive"))
      (node (ref "R3") (pin "1") (pinfunction "1_1") (pintype "passive"))
      (node (ref "R31") (pin "1") (pinfunction "1_1") (pintype "passive"))
      (node (ref "R32") (pin "1") (pinfunction "1_1") (pintype "passive"))
      (node (ref "R35") (pin "2") (pinfunction "2_2") (pintype "passive"))
      (node (ref "R7") (pin "2") (pinfunction "2_2") (pintype "passive"))
      (node (ref "SW1") (pin "3") (pinfunction "P1_3") (pintype "passive"))
      (node (ref "U1") (pin "116") (pinfunction "AGND_116") (pintype "bidirectional"))
      (node (ref "U1") (pin "P$1") (pinfunction "PAD_P$1") (pintype "bidirectional"))
      (node (ref "U2") (pin "2") (pinfunction "GND_2") (pintype "bidirectional"))
      (node (ref "U3") (pin "2") (pinfunction "GND_2") (pintype "bidirectional"))
      (node (ref "U4") (pin "2") (pinfunction "GND_2") (pintype "bidirectional"))
      (node (ref "U5") (pin "1") (pinfunction "VSS_1") (pintype "power_in"))
      (node (ref "U6") (pin "16") (pinfunction "PGND3_16") (pintype "power_in"))
      (node (ref "U6") (pin "22") (pinfunction "AGND_22") (pintype "power_in"))
      (node (ref "U6") (pin "46") (pinfunction "PGND1_46") (pintype "power_in"))
      (node (ref "U6") (pin "49") (pinfunction "EP_49") (pintype "power_in"))
      (node (ref "U6") (pin "9") (pinfunction "PGND2_9") (pintype "power_in"))
    )
    (net (code "12") (name "IPSOUT") (class "Default")
      (node (ref "C49") (pin "1") (pinfunction "1_1") (pintype "passive"))
      (node (ref "C53") (pin "2") (pinfunction "2_2") (pintype "passive"))
      (node (ref "C59") (pin "1") (pinfunction "1_1") (pintype "passive"))
      (node (ref "C60") (pin "1") (pinfunction "1_1") (pintype "passive"))
      (node (ref "C63") (pin "2") (pinfunction "2_2") (pintype "passive"))
      (node (ref "C64") (pin "2") (pinfunction "2_2") (pintype "passive"))
      (node (ref "U6") (pin "13") (pinfunction "LDO24IN_13") (pintype "power_in"))
      (node (ref "U6") (pin "14") (pinfunction "VIN3_14") (pintype "power_in"))
      (node (ref "U6") (pin "21") (pinfunction "APS_21") (pintype "power_in"))
      (node (ref "U6") (pin "34") (pinfunction "IPSOUT_34") (pintype "bidirectional"))
      (node (ref "U6") (pin "35") (pinfunction "IPSOUT_35") (pintype "bidirectional"))
      (node (ref "U6") (pin "40") (pinfunction "LDO3IN_40") (pintype "output"))
      (node (ref "U6") (pin "44") (pinfunction "VIN1_44") (pintype "power_in"))
      (node (ref "U6") (pin "7") (pinfunction "VIN2_7") (pintype "power_in"))
    )
    (net (code "13") (name "LDO1V8") (class "Default")
      (node (ref "C48") (pin "1") (pinfunction "1_1") (pintype "passive"))
      (node (ref "U6") (pin "41") (pinfunction "LDO3_41") (pintype "input"))
    )
    (net (code "14") (name "LDO3V") (class "Default")
      (node (ref "C47") (pin "1") (pinfunction "1_1") (pintype "passive"))
      (node (ref "U6") (pin "12") (pinfunction "LDO2_12") (pintype "output"))
    )
    (net (code "15") (name "LDO13V3") (class "Default")
      (node (ref "C46") (pin "1") (pinfunction "1_1") (pintype "passive"))
      (node (ref "U6") (pin "28") (pinfunction "LDO1_28") (pintype "output"))
    )
    (net (code "16") (name "LDO42V8") (class "Default")
      (node (ref "C50") (pin "1") (pinfunction "1_1") (pintype "passive"))
      (node (ref "U6") (pin "11") (pinfunction "LDO4_11") (pintype "output"))
    )
    (net (code "17") (name "LED0") (class "Default")
      (node (ref "R18") (pin "1") (pinfunction "1_1") (pintype "passive"))
      (node (ref "U1") (pin "4") (pinfunction "PG1/SDC1/CMD_4") (pintype "bidirectional"))
    )
    (net (code "18") (name "LED1") (class "Default")
      (node (ref "R19") (pin "1") (pinfunction "1_1") (pintype "passive"))
      (node (ref "U1") (pin "5") (pinfunction "PG0/SDC1/CLK_5") (pintype "bidirectional"))
    )
    (net (code "19") (name "LED2") (class "Default")
      (node (ref "R17") (pin "1") (pinfunction "1_1") (pintype "passive"))
      (node (ref "U1") (pin "3") (pinfunction "PG2/SDC1/D0_3") (pintype "bidirectional"))
    )
    (net (code "20") (name "LED3") (class "Default")
      (node (ref "R1") (pin "1") (pinfunction "1_1") (pintype "passive"))
      (node (ref "U1") (pin "78") (pinfunction "EPHY_SPD_LED_78") (pintype "bidirectional"))
    )
    (net (code "21") (name "LED4") (class "Default")
      (node (ref "R2") (pin "1") (pinfunction "1_1") (pintype "passive"))
      (node (ref "U1") (pin "77") (pinfunction "EPHY_LINK_LED_77") (pintype "bidirectional"))
    )
    (net (code "22") (name "N$32") (class "Default")
      (node (ref "R34") (pin "1") (pinfunction "1_1") (pintype "passive"))
    )
    (net (code "23") (name "N$34") (class "Default")
      (node (ref "U1") (pin "97") (pinfunction "RTC-VIO_97") (pintype "bidirectional"))
    )
    (net (code "24") (name "N$40") (class "Default")
      (node (ref "U6") (pin "27") (pinfunction "LDO1SET_27") (pintype "input"))
    )
    (net (code "25") (name "N$42") (class "Default")
      (node (ref "U1") (pin "73") (pinfunction "SZQ_73") (pintype "bidirectional"))
    )
    (net (code "26") (name "N$43") (class "Default")
      (node (ref "U1") (pin "71") (pinfunction "SVREF0_71") (pintype "bidirectional"))
    )
    (net (code "27") (name "N$44") (class "Default")
      (node (ref "U1") (pin "63") (pinfunction "SVREF1_63") (pintype "bidirectional"))
    )
    (net (code "28") (name "N$51") (class "Default")
      (node (ref "C67") (pin "2") (pinfunction "2_2") (pintype "passive"))
      (node (ref "R34") (pin "2") (pinfunction "2_2") (pintype "passive"))
      (node (ref "U6") (pin "25") (pinfunction "PWROK_25") (pintype "output"))
    )
    (net (code "29") (name "NMI_N") (class "Default")
      (node (ref "U6") (pin "48") (pinfunction "IRQ/WAKEUP_48") (pintype "bidirectional"))
    )
    (net (code "30") (name "Net-(CS-2)") (class "Default")
      (node (ref "CS") (pin "1") (pinfunction "2_1") (pintype "passive"))
      (node (ref "U1") (pin "54") (pinfunction "PC2/SPI1/CS_54") (pintype "bidirectional"))
    )
    (net (code "31") (name "Net-(D1-CATHODE_BLUE)") (class "Default")
      (node (ref "D1") (pin "4") (pinfunction "CATHODE_BLUE_4") (pintype "passive"))
      (node (ref "R3") (pin "2") (pinfunction "2_2") (pintype "passive"))
    )
    (net (code "32") (name "Net-(D1-CATHODE_GREEN)") (class "Default")
      (node (ref "D1") (pin "3") (pinfunction "CATHODE_GREEN_3") (pintype "passive"))
      (node (ref "R2") (pin "2") (pinfunction "2_2") (pintype "passive"))
    )
    (net (code "33") (name "Net-(D1-CATHODE_RED)") (class "Default")
      (node (ref "D1") (pin "2") (pinfunction "CATHODE_RED_2") (pintype "passive"))
      (node (ref "R1") (pin "2") (pinfunction "2_2") (pintype "passive"))
    )
    (net (code "34") (name "Net-(D2-CATHODE_BLUE)") (class "Default")
      (node (ref "D2") (pin "4") (pinfunction "CATHODE_BLUE_4") (pintype "passive"))
      (node (ref "R17") (pin "2") (pinfunction "2_2") (pintype "passive"))
    )
    (net (code "35") (name "Net-(D2-CATHODE_GREEN)") (class "Default")
      (node (ref "D2") (pin "3") (pinfunction "CATHODE_GREEN_3") (pintype "passive"))
      (node (ref "R18") (pin "2") (pinfunction "2_2") (pintype "passive"))
    )
    (net (code "36") (name "Net-(D2-CATHODE_RED)") (class "Default")
      (node (ref "D2") (pin "2") (pinfunction "CATHODE_RED_2") (pintype "passive"))
      (node (ref "R19") (pin "2") (pinfunction "2_2") (pintype "passive"))
    )
    (net (code "37") (name "Net-(J1-DM)") (class "Default")
      (node (ref "J1") (pin "2") (pinfunction "DM_2") (pintype "passive"))
      (node (ref "U1") (pin "110") (pinfunction "USB-DM_110") (pintype "bidirectional"))
    )
    (net (code "38") (name "Net-(J1-DP)") (class "Default")
      (node (ref "J1") (pin "3") (pinfunction "DP_3") (pintype "passive"))
      (node (ref "U1") (pin "111") (pinfunction "USB-DP_111") (pintype "bidirectional"))
    )
    (net (code "39") (name "Net-(J1-ID)") (class "Default")
      (node (ref "J1") (pin "4") (pinfunction "ID_4") (pintype "passive"))
      (node (ref "R20") (pin "2") (pinfunction "2_2") (pintype "passive"))
    )
    (net (code "40") (name "Net-(L1-1)") (class "Default")
      (node (ref "C5") (pin "2") (pinfunction "2_2") (pintype "passive"))
      (node (ref "L1") (pin "P$1") (pinfunction "1_P$1") (pintype "passive"))
      (node (ref "U2") (pin "3") (pinfunction "SW_3") (pintype "bidirectional"))
    )
    (net (code "41") (name "Net-(L2-1)") (class "Default")
      (node (ref "C10") (pin "2") (pinfunction "2_2") (pintype "passive"))
      (node (ref "L2") (pin "P$1") (pinfunction "1_P$1") (pintype "passive"))
      (node (ref "U3") (pin "3") (pinfunction "SW_3") (pintype "bidirectional"))
    )
    (net (code "42") (name "Net-(L3-1)") (class "Default")
      (node (ref "C15") (pin "2") (pinfunction "2_2") (pintype "passive"))
      (node (ref "L3") (pin "P$1") (pinfunction "1_P$1") (pintype "passive"))
      (node (ref "U4") (pin "3") (pinfunction "SW_3") (pintype "bidirectional"))
    )
    (net (code "43") (name "Net-(L4-1)") (class "Default")
      (node (ref "L4") (pin "P$1") (pinfunction "1_P$1") (pintype "passive"))
      (node (ref "U6") (pin "8") (pinfunction "LX2_8") (pintype "bidirectional"))
    )
    (net (code "44") (name "Net-(L5-1)") (class "Default")
      (node (ref "L5") (pin "P$1") (pinfunction "1_P$1") (pintype "passive"))
      (node (ref "U6") (pin "15") (pinfunction "LX3_15") (pintype "bidirectional"))
    )
    (net (code "45") (name "Net-(L6-1)") (class "Default")
      (node (ref "L6") (pin "P$1") (pinfunction "1_P$1") (pintype "passive"))
      (node (ref "U6") (pin "45") (pinfunction "LX1_45") (pintype "bidirectional"))
    )
    (net (code "46") (name "Net-(L6-2)") (class "Default")
      (node (ref "C56") (pin "1") (pinfunction "1_1") (pintype "passive"))
      (node (ref "C58") (pin "1") (pinfunction "1_1") (pintype "passive"))
      (node (ref "L6") (pin "P$2") (pinfunction "2_P$2") (pintype "passive"))
      (node (ref "R33") (pin "1") (pinfunction "1_1") (pintype "passive"))
      (node (ref "U6") (pin "43") (pinfunction "CHSENSE_43") (pintype "output"))
    )
    (net (code "47") (name "Net-(MISO-2)") (class "Default")
      (node (ref "MISO") (pin "1") (pinfunction "2_1") (pintype "passive"))
      (node (ref "U1") (pin "52") (pinfunction "PC0/SPI1/MISO_52") (pintype "bidirectional"))
    )
    (net (code "48") (name "Net-(MOSI-2)") (class "Default")
      (node (ref "MOSI") (pin "1") (pinfunction "2_1") (pintype "passive"))
      (node (ref "U1") (pin "55") (pinfunction "PC3/SPI1/MOSI_55") (pintype "bidirectional"))
    )
    (net (code "49") (name "Net-(PWM0-2)") (class "Default")
      (node (ref "PWM0") (pin "1") (pinfunction "2_1") (pintype "passive"))
      (node (ref "U1") (pin "43") (pinfunction "PB4/PWM0_43") (pintype "bidirectional"))
    )
    (net (code "50") (name "Net-(PWM1-2)") (class "Default")
      (node (ref "PWM1") (pin "1") (pinfunction "2_1") (pintype "passive"))
      (node (ref "U1") (pin "44") (pinfunction "PB5/PWM1_44") (pintype "bidirectional"))
    )
    (net (code "51") (name "Net-(R5-Pad1)") (class "Default")
      (node (ref "R5") (pin "1") (pinfunction "1_1") (pintype "passive"))
      (node (ref "R6") (pin "2") (pinfunction "2_2") (pintype "passive"))
      (node (ref "R7") (pin "1") (pinfunction "1_1") (pintype "passive"))
    )
    (net (code "52") (name "Net-(R10-Pad2)") (class "Default")
      (node (ref "R10") (pin "2") (pinfunction "2_2") (pintype "passive"))
      (node (ref "R11") (pin "1") (pinfunction "1_1") (pintype "passive"))
      (node (ref "R9") (pin "1") (pinfunction "1_1") (pintype "passive"))
    )
    (net (code "53") (name "Net-(R13-Pad1)") (class "Default")
      (node (ref "R13") (pin "1") (pinfunction "1_1") (pintype "passive"))
      (node (ref "R14") (pin "2") (pinfunction "2_2") (pintype "passive"))
      (node (ref "R15") (pin "1") (pinfunction "1_1") (pintype "passive"))
    )
    (net (code "54") (name "Net-(RX1-2)") (class "Default")
      (node (ref "RX1") (pin "1") (pinfunction "2_1") (pintype "passive"))
      (node (ref "U1") (pin "8") (pinfunction "PE22/UART1/RX_8") (pintype "bidirectional"))
    )
    (net (code "55") (name "Net-(RX2-2)") (class "Default")
      (node (ref "RX2") (pin "1") (pinfunction "2_1") (pintype "passive"))
      (node (ref "U1") (pin "40") (pinfunction "PB1/UART2/RX_40") (pintype "bidirectional"))
    )
    (net (code "56") (name "Net-(SCK-2)") (class "Default")
      (node (ref "SCK") (pin "1") (pinfunction "2_1") (pintype "passive"))
      (node (ref "U1") (pin "53") (pinfunction "PC1/SPI1/SCK_53") (pintype "bidirectional"))
    )
    (net (code "57") (name "Net-(SCL0-2)") (class "Default")
      (node (ref "R27") (pin "2") (pinfunction "2_2") (pintype "passive"))
      (node (ref "SCL0") (pin "1") (pinfunction "2_1") (pintype "passive"))
      (node (ref "U1") (pin "45") (pinfunction "PB6/I2C0/SCL_45") (pintype "bidirectional"))
    )
    (net (code "58") (name "Net-(SDA0-2)") (class "Default")
      (node (ref "R28") (pin "2") (pinfunction "2_2") (pintype "passive"))
      (node (ref "SDA0") (pin "1") (pinfunction "2_1") (pintype "passive"))
      (node (ref "U1") (pin "46") (pinfunction "PB7/I2C0/SDA_46") (pintype "bidirectional"))
    )
    (net (code "59") (name "Net-(SW1-S1)") (class "Default")
      (node (ref "R36") (pin "2") (pinfunction "2_2") (pintype "passive"))
      (node (ref "SW1") (pin "4") (pinfunction "S1_4") (pintype "passive"))
    )
    (net (code "60") (name "Net-(TX1-2)") (class "Default")
      (node (ref "TX1") (pin "1") (pinfunction "2_1") (pintype "passive"))
      (node (ref "U1") (pin "9") (pinfunction "PE21/UART1/TX_9") (pintype "bidirectional"))
    )
    (net (code "61") (name "Net-(TX2-2)") (class "Default")
      (node (ref "TX2") (pin "1") (pinfunction "2_1") (pintype "passive"))
      (node (ref "U1") (pin "39") (pinfunction "PB0/UART2/TX_39") (pintype "bidirectional"))
    )
    (net (code "62") (name "Net-(U1C-MCSI-CKN)") (class "Default")
      (node (ref "P2") (pin "8") (pinfunction "8_8") (pintype "bidirectional"))
      (node (ref "U1") (pin "87") (pinfunction "MCSI-CKN_87") (pintype "bidirectional"))
    )
    (net (code "63") (name "Net-(U1C-MCSI-CKP)") (class "Default")
      (node (ref "P2") (pin "9") (pinfunction "9_9") (pintype "bidirectional"))
      (node (ref "U1") (pin "86") (pinfunction "MCSI-CKP_86") (pintype "bidirectional"))
    )
    (net (code "64") (name "Net-(U1C-MCSI-D0N)") (class "Default")
      (node (ref "P2") (pin "2") (pinfunction "2_2") (pintype "bidirectional"))
      (node (ref "U1") (pin "82") (pinfunction "MCSI-D0N_82") (pintype "bidirectional"))
    )
    (net (code "65") (name "Net-(U1C-MCSI-D0P)") (class "Default")
      (node (ref "P2") (pin "3") (pinfunction "3_3") (pintype "bidirectional"))
      (node (ref "U1") (pin "81") (pinfunction "MCSI-D0P_81") (pintype "bidirectional"))
    )
    (net (code "66") (name "Net-(U1C-MCSI-D1N)") (class "Default")
      (node (ref "P2") (pin "5") (pinfunction "5_5") (pintype "bidirectional"))
      (node (ref "U1") (pin "84") (pinfunction "MCSI-D1N_84") (pintype "bidirectional"))
    )
    (net (code "67") (name "Net-(U1C-MCSI-D1P)") (class "Default")
      (node (ref "P2") (pin "6") (pinfunction "6_6") (pintype "bidirectional"))
      (node (ref "U1") (pin "83") (pinfunction "MCSI-D1P_83") (pintype "bidirectional"))
    )
    (net (code "68") (name "Net-(U1D-X24MIN)") (class "Default")
      (node (ref "C4") (pin "1") (pinfunction "1_1") (pintype "passive"))
      (node (ref "U1") (pin "75") (pinfunction "X24MIN_75") (pintype "bidirectional"))
      (node (ref "X1") (pin "P$3") (pinfunction "2_P$3") (pintype "passive"))
    )
    (net (code "69") (name "Net-(U1D-X24MOUNT)") (class "Default")
      (node (ref "C3") (pin "1") (pinfunction "1_1") (pintype "passive"))
      (node (ref "U1") (pin "74") (pinfunction "X24MOUNT_74") (pintype "bidirectional"))
      (node (ref "X1") (pin "P$1") (pinfunction "1_P$1") (pintype "passive"))
    )
    (net (code "70") (name "Net-(U1D-X32KIN)") (class "Default")
      (node (ref "C2") (pin "1") (pinfunction "1_1") (pintype "passive"))
      (node (ref "U1") (pin "96") (pinfunction "X32KIN_96") (pintype "bidirectional"))
      (node (ref "X2") (pin "P$1") (pinfunction "1_P$1") (pintype "passive"))
    )
    (net (code "71") (name "Net-(U1D-X32KOUT)") (class "Default")
      (node (ref "C1") (pin "1") (pinfunction "1_1") (pintype "passive"))
      (node (ref "U1") (pin "95") (pinfunction "X32KOUT_95") (pintype "bidirectional"))
      (node (ref "X2") (pin "P$2") (pinfunction "2_P$2") (pintype "passive"))
    )
    (net (code "72") (name "Net-(U1F-VCC-RTC)") (class "Default")
      (node (ref "R16") (pin "1") (pinfunction "1_1") (pintype "passive"))
      (node (ref "U1") (pin "98") (pinfunction "VCC-RTC_98") (pintype "bidirectional"))
    )
    (net (code "73") (name "Net-(U2-BST)") (class "Default")
      (node (ref "C5") (pin "1") (pinfunction "1_1") (pintype "passive"))
      (node (ref "U2") (pin "4") (pinfunction "BST_4") (pintype "bidirectional"))
    )
    (net (code "74") (name "Net-(U2-ENABLE)") (class "Default")
      (node (ref "R4") (pin "1") (pinfunction "1_1") (pintype "passive"))
      (node (ref "U2") (pin "5") (pinfunction "ENABLE_5") (pintype "bidirectional"))
    )
    (net (code "75") (name "Net-(U2-FB)") (class "Default")
      (node (ref "R5") (pin "2") (pinfunction "2_2") (pintype "passive"))
      (node (ref "U2") (pin "6") (pinfunction "FB_6") (pintype "bidirectional"))
    )
    (net (code "76") (name "Net-(U3-BST)") (class "Default")
      (node (ref "C10") (pin "1") (pinfunction "1_1") (pintype "passive"))
      (node (ref "U3") (pin "4") (pinfunction "BST_4") (pintype "bidirectional"))
    )
    (net (code "77") (name "Net-(U3-ENABLE)") (class "Default")
      (node (ref "R8") (pin "1") (pinfunction "1_1") (pintype "passive"))
      (node (ref "U3") (pin "5") (pinfunction "ENABLE_5") (pintype "bidirectional"))
    )
    (net (code "78") (name "Net-(U3-FB)") (class "Default")
      (node (ref "R9") (pin "2") (pinfunction "2_2") (pintype "passive"))
      (node (ref "U3") (pin "6") (pinfunction "FB_6") (pintype "bidirectional"))
    )
    (net (code "79") (name "Net-(U4-BST)") (class "Default")
      (node (ref "C15") (pin "1") (pinfunction "1_1") (pintype "passive"))
      (node (ref "U4") (pin "4") (pinfunction "BST_4") (pintype "bidirectional"))
    )
    (net (code "80") (name "Net-(U4-ENABLE)") (class "Default")
      (node (ref "R12") (pin "1") (pinfunction "1_1") (pintype "passive"))
      (node (ref "U4") (pin "5") (pinfunction "ENABLE_5") (pintype "bidirectional"))
    )
    (net (code "81") (name "Net-(U4-FB)") (class "Default")
      (node (ref "R13") (pin "2") (pinfunction "2_2") (pintype "passive"))
      (node (ref "U4") (pin "6") (pinfunction "FB_6") (pintype "bidirectional"))
    )
    (net (code "82") (name "Net-(U6-BIAS)") (class "Default")
      (node (ref "R31") (pin "2") (pinfunction "2_2") (pintype "passive"))
      (node (ref "U6") (pin "23") (pinfunction "BIAS_23") (pintype "bidirectional"))
    )
    (net (code "83") (name "Net-(U6-N_OE)") (class "Default")
      (node (ref "R35") (pin "1") (pinfunction "1_1") (pintype "passive"))
      (node (ref "U6") (pin "4") (pinfunction "N_OE_4") (pintype "input"))
    )
    (net (code "84") (name "Net-(U6-PWRON)") (class "Default")
      (node (ref "C68") (pin "1") (pinfunction "1_1") (pintype "passive"))
      (node (ref "R36") (pin "1") (pinfunction "1_1") (pintype "passive"))
      (node (ref "U6") (pin "47") (pinfunction "PWRON_47") (pintype "input"))
    )
    (net (code "85") (name "Net-(U6-SCK)") (class "Default")
      (node (ref "R38") (pin "1") (pinfunction "1_1") (pintype "passive"))
      (node (ref "U6") (pin "2") (pinfunction "SCK_2") (pintype "input"))
    )
    (net (code "86") (name "Net-(U6-SDA)") (class "Default")
      (node (ref "R37") (pin "1") (pinfunction "1_1") (pintype "passive"))
      (node (ref "U6") (pin "1") (pinfunction "SDA_1") (pintype "bidirectional"))
    )
    (net (code "87") (name "Net-(U6-TS)") (class "Default")
      (node (ref "R32") (pin "2") (pinfunction "2_2") (pintype "passive"))
      (node (ref "U6") (pin "37") (pinfunction "TS_37") (pintype "input"))
    )
    (net (code "88") (name "Net-(U6-VINT)") (class "Default")
      (node (ref "C65") (pin "2") (pinfunction "2_2") (pintype "passive"))
      (node (ref "U6") (pin "26") (pinfunction "VINT_26") (pintype "power_in"))
    )
    (net (code "89") (name "Net-(U6-VREF)") (class "Default")
      (node (ref "C66") (pin "2") (pinfunction "2_2") (pintype "passive"))
      (node (ref "U6") (pin "24") (pinfunction "VREF_24") (pintype "output"))
    )
    (net (code "90") (name "SCL") (class "Default")
      (node (ref "P2") (pin "13") (pinfunction "13_13") (pintype "bidirectional"))
      (node (ref "R29") (pin "2") (pinfunction "2_2") (pintype "passive"))
      (node (ref "R38") (pin "2") (pinfunction "2_2") (pintype "passive"))
      (node (ref "SCL1") (pin "1") (pinfunction "2_1") (pintype "passive"))
      (node (ref "U1") (pin "48") (pinfunction "PB8/I2C1/SCL_48") (pintype "bidirectional"))
    )
    (net (code "91") (name "SDA") (class "Default")
      (node (ref "P2") (pin "14") (pinfunction "14_14") (pintype "bidirectional"))
      (node (ref "R30") (pin "2") (pinfunction "2_2") (pintype "passive"))
      (node (ref "R37") (pin "2") (pinfunction "2_2") (pintype "passive"))
      (node (ref "SDA1") (pin "1") (pinfunction "2_1") (pintype "passive"))
      (node (ref "U1") (pin "49") (pinfunction "PB9/I2C1/SDA_49") (pintype "bidirectional"))
    )
    (net (code "92") (name "SDC0_CLK") (class "Default")
      (node (ref "J3") (pin "5") (pinfunction "CLK_5") (pintype "bidirectional"))
      (node (ref "R26") (pin "1") (pinfunction "1_1") (pintype "passive"))
      (node (ref "U1") (pin "105") (pinfunction "PF2/SDC0/CLK_105") (pintype "bidirectional"))
    )
    (net (code "93") (name "SDC0_CMD") (class "Default")
      (node (ref "J3") (pin "3") (pinfunction "CMD_3") (pintype "bidirectional"))
      (node (ref "R25") (pin "1") (pinfunction "1_1") (pintype "passive"))
      (node (ref "U1") (pin "103") (pinfunction "PF3/SDC0/CMD_103") (pintype "bidirectional"))
    )
    (net (code "94") (name "SDC0_D0") (class "Default")
      (node (ref "J3") (pin "7") (pinfunction "DAT0_7") (pintype "bidirectional"))
      (node (ref "R21") (pin "1") (pinfunction "1_1") (pintype "passive"))
      (node (ref "U1") (pin "106") (pinfunction "PF1/SDC0/D0_106") (pintype "bidirectional"))
    )
    (net (code "95") (name "SDC0_D1") (class "Default")
      (node (ref "J3") (pin "8") (pinfunction "DAT1_8") (pintype "bidirectional"))
      (node (ref "R22") (pin "1") (pinfunction "1_1") (pintype "passive"))
      (node (ref "U1") (pin "107") (pinfunction "PF0/SDC0/D1_107") (pintype "bidirectional"))
    )
    (net (code "96") (name "SDC0_D2") (class "Default")
      (node (ref "J3") (pin "1") (pinfunction "DAT2_1") (pintype "bidirectional"))
      (node (ref "R23") (pin "1") (pinfunction "1_1") (pintype "passive"))
      (node (ref "U1") (pin "101") (pinfunction "PF5/SDC0/D2_101") (pintype "bidirectional"))
    )
    (net (code "97") (name "SDC0_D3") (class "Default")
      (node (ref "J3") (pin "2") (pinfunction "DAT3/CD_2") (pintype "bidirectional"))
      (node (ref "R24") (pin "1") (pinfunction "1_1") (pintype "passive"))
      (node (ref "U1") (pin "102") (pinfunction "PF4/SDC0/D3_102") (pintype "bidirectional"))
    )
    (net (code "98") (name "USB0_DRV") (class "Default")
      (node (ref "U6") (pin "6") (pinfunction "N_VBUSEN_6") (pintype "input"))
    )
    (net (code "99") (name "USBVBUS") (class "Default")
      (node (ref "C51") (pin "2") (pinfunction "2_2") (pintype "passive"))
      (node (ref "R39") (pin "1") (pinfunction "1_1") (pintype "passive"))
      (node (ref "U6") (pin "31") (pinfunction "VBUS_31") (pintype "power_in"))
    )
    (net (code "100") (name "VBAT") (class "Default")
      (node (ref "C57") (pin "1") (pinfunction "1_1") (pintype "passive"))
      (node (ref "C58") (pin "2") (pinfunction "2_2") (pintype "passive"))
      (node (ref "CN1") (pin "1") (pinfunction "2_1") (pintype "passive"))
      (node (ref "R33") (pin "2") (pinfunction "2_2") (pintype "passive"))
      (node (ref "U6") (pin "38") (pinfunction "BAT_38") (pintype "power_in"))
      (node (ref "U6") (pin "39") (pinfunction "BAT_39") (pintype "power_in"))
      (node (ref "U6") (pin "42") (pinfunction "BATSENSE_42") (pintype "input"))
    )
    (net (code "101") (name "VCC") (class "Default")
      (node (ref "5V") (pin "P$1") (pinfunction "1_P$1") (pintype "bidirectional"))
      (node (ref "C11") (pin "1") (pinfunction "1_1") (pintype "passive"))
      (node (ref "C12") (pin "1") (pinfunction "+_1") (pintype "passive"))
      (node (ref "C16") (pin "1") (pinfunction "1_1") (pintype "passive"))
      (node (ref "C17") (pin "1") (pinfunction "+_1") (pintype "passive"))
      (node (ref "C21") (pin "1") (pinfunction "1_1") (pintype "passive"))
      (node (ref "C6") (pin "1") (pinfunction "1_1") (pintype "passive"))
      (node (ref "C7") (pin "1") (pinfunction "+_1") (pintype "passive"))
      (node (ref "J1") (pin "1") (pinfunction "VCC_1") (pintype "passive"))
      (node (ref "R12") (pin "2") (pinfunction "2_2") (pintype "passive"))
      (node (ref "R4") (pin "2") (pinfunction "2_2") (pintype "passive"))
      (node (ref "R8") (pin "2") (pinfunction "2_2") (pintype "passive"))
      (node (ref "U2") (pin "1") (pinfunction "VIN_1") (pintype "bidirectional"))
      (node (ref "U3") (pin "1") (pinfunction "VIN_1") (pintype "bidirectional"))
      (node (ref "U4") (pin "1") (pinfunction "VIN_1") (pintype "bidirectional"))
    )
    (net (code "102") (name "unconnected-(J3-DET-Pad11)") (class "Default")
      (node (ref "J3") (pin "11") (pinfunction "DET_11") (pintype "passive"))
    )
    (net (code "103") (name "unconnected-(J3-POL-Pad12)") (class "Default")
      (node (ref "J3") (pin "12") (pinfunction "POL_12") (pintype "passive"))
    )
    (net (code "104") (name "unconnected-(SW1-P-Pad1)") (class "Default")
      (node (ref "SW1") (pin "1") (pinfunction "P_1") (pintype "passive"))
    )
    (net (code "105") (name "unconnected-(SW1-S-Pad2)") (class "Default")
      (node (ref "SW1") (pin "2") (pinfunction "S_2") (pintype "passive"))
    )
    (net (code "106") (name "unconnected-(U1A-HBIAS-Pad119)") (class "Default")
      (node (ref "U1") (pin "119") (pinfunction "HBIAS_119") (pintype "bidirectional"))
    )
    (net (code "107") (name "unconnected-(U1A-HPCOM-Pad125)") (class "Default")
      (node (ref "U1") (pin "125") (pinfunction "HPCOM_125") (pintype "bidirectional"))
    )
    (net (code "108") (name "unconnected-(U1A-HPCOMFB-Pad124)") (class "Default")
      (node (ref "U1") (pin "124") (pinfunction "HPCOMFB_124") (pintype "bidirectional"))
    )
    (net (code "109") (name "unconnected-(U1A-HPOUTL-Pad121)") (class "Default")
      (node (ref "U1") (pin "121") (pinfunction "HPOUTL_121") (pintype "bidirectional"))
    )
    (net (code "110") (name "unconnected-(U1A-HPOUTR-Pad120)") (class "Default")
      (node (ref "U1") (pin "120") (pinfunction "HPOUTR_120") (pintype "bidirectional"))
    )
    (net (code "111") (name "unconnected-(U1A-HPVCCBP-Pad123)") (class "Default")
      (node (ref "U1") (pin "123") (pinfunction "HPVCCBP_123") (pintype "bidirectional"))
    )
    (net (code "112") (name "unconnected-(U1A-HPVCCIN-Pad122)") (class "Default")
      (node (ref "U1") (pin "122") (pinfunction "HPVCCIN_122") (pintype "bidirectional"))
    )
    (net (code "113") (name "unconnected-(U1A-MICIN1N-Pad114)") (class "Default")
      (node (ref "U1") (pin "114") (pinfunction "MICIN1N_114") (pintype "bidirectional"))
    )
    (net (code "114") (name "unconnected-(U1A-MICIN1P-Pad113)") (class "Default")
      (node (ref "U1") (pin "113") (pinfunction "MICIN1P_113") (pintype "bidirectional"))
    )
    (net (code "115") (name "unconnected-(U1A-VRA1-Pad117)") (class "Default")
      (node (ref "U1") (pin "117") (pinfunction "VRA1_117") (pintype "bidirectional"))
    )
    (net (code "116") (name "unconnected-(U1A-VRA2-Pad118)") (class "Default")
      (node (ref "U1") (pin "118") (pinfunction "VRA2_118") (pintype "bidirectional"))
    )
    (net (code "117") (name "unconnected-(U1B-LRADC0-Pad112)") (class "Default")
      (node (ref "U1") (pin "112") (pinfunction "LRADC0_112") (pintype "bidirectional"))
    )
    (net (code "118") (name "unconnected-(U1B-PB2-Pad41)") (class "Default")
      (node (ref "U1") (pin "41") (pinfunction "PB2_41") (pintype "bidirectional"))
    )
    (net (code "119") (name "unconnected-(U1B-PB3-Pad42)") (class "Default")
      (node (ref "U1") (pin "42") (pinfunction "PB3_42") (pintype "bidirectional"))
    )
    (net (code "120") (name "unconnected-(U1B-PE0{slash}CSI-CLK-{slash}LCD-CLK-Pad37)") (class "Default")
      (node (ref "U1") (pin "37") (pinfunction "PE0/CSI-CLK-/LCD-CLK_37") (pintype "bidirectional"))
    )
    (net (code "121") (name "unconnected-(U1B-PE1{slash}CSI-MCLK{slash}LCD-DE-Pad36)") (class "Default")
      (node (ref "U1") (pin "36") (pinfunction "PE1/CSI-MCLK/LCD-DE_36") (pintype "bidirectional"))
    )
    (net (code "122") (name "unconnected-(U1B-PE2{slash}CSI-HSYNC{slash}LCD-HSYNC-Pad35)") (class "Default")
      (node (ref "U1") (pin "35") (pinfunction "PE2/CSI-HSYNC/LCD-HSYNC_35") (pintype "bidirectional"))
    )
    (net (code "123") (name "unconnected-(U1B-PE3{slash}CSI-VSYNC{slash}LCD-VSYNC-Pad34)") (class "Default")
      (node (ref "U1") (pin "34") (pinfunction "PE3/CSI-VSYNC/LCD-VSYNC_34") (pintype "bidirectional"))
    )
    (net (code "124") (name "unconnected-(U1B-PE4{slash}CSI-D0{slash}LCD-D2-Pad33)") (class "Default")
      (node (ref "U1") (pin "33") (pinfunction "PE4/CSI-D0/LCD-D2_33") (pintype "bidirectional"))
    )
    (net (code "125") (name "unconnected-(U1B-PE5{slash}CSI-D1{slash}-LCD-D3-Pad32)") (class "Default")
      (node (ref "U1") (pin "32") (pinfunction "PE5/CSI-D1/-LCD-D3_32") (pintype "bidirectional"))
    )
    (net (code "126") (name "unconnected-(U1B-PE6{slash}CSI-D2{slash}LCD-D4-Pad31)") (class "Default")
      (node (ref "U1") (pin "31") (pinfunction "PE6/CSI-D2/LCD-D4_31") (pintype "bidirectional"))
    )
    (net (code "127") (name "unconnected-(U1B-PE7{slash}CSI-D3{slash}LCD-D5-Pad30)") (class "Default")
      (node (ref "U1") (pin "30") (pinfunction "PE7/CSI-D3/LCD-D5_30") (pintype "bidirectional"))
    )
    (net (code "128") (name "unconnected-(U1B-PE8{slash}CSI-D4{slash}LCD-D6-Pad28)") (class "Default")
      (node (ref "U1") (pin "28") (pinfunction "PE8/CSI-D4/LCD-D6_28") (pintype "bidirectional"))
    )
    (net (code "129") (name "unconnected-(U1B-PE9{slash}CSI-D5{slash}LCD-D7-Pad27)") (class "Default")
      (node (ref "U1") (pin "27") (pinfunction "PE9/CSI-D5/LCD-D7_27") (pintype "bidirectional"))
    )
    (net (code "130") (name "unconnected-(U1B-PE10{slash}CSI-D6{slash}LCD-D10-Pad24)") (class "Default")
      (node (ref "U1") (pin "24") (pinfunction "PE10/CSI-D6/LCD-D10_24") (pintype "bidirectional"))
    )
    (net (code "131") (name "unconnected-(U1B-PE11{slash}CSI-D7{slash}LCD-D11-Pad23)") (class "Default")
      (node (ref "U1") (pin "23") (pinfunction "PE11/CSI-D7/LCD-D11_23") (pintype "bidirectional"))
    )
    (net (code "132") (name "unconnected-(U1B-PE12{slash}CSI-D8{slash}LCD-D12-Pad22)") (class "Default")
      (node (ref "U1") (pin "22") (pinfunction "PE12/CSI-D8/LCD-D12_22") (pintype "bidirectional"))
    )
    (net (code "133") (name "unconnected-(U1B-PE13{slash}CSI-D9{slash}LCD-D13-Pad18)") (class "Default")
      (node (ref "U1") (pin "18") (pinfunction "PE13/CSI-D9/LCD-D13_18") (pintype "bidirectional"))
    )
    (net (code "134") (name "unconnected-(U1B-PE14{slash}CSI-D10{slash}LCD-D14-Pad17)") (class "Default")
      (node (ref "U1") (pin "17") (pinfunction "PE14/CSI-D10/LCD-D14_17") (pintype "bidirectional"))
    )
    (net (code "135") (name "unconnected-(U1B-PE15{slash}CSI-D11{slash}LCD-D15-Pad16)") (class "Default")
      (node (ref "U1") (pin "16") (pinfunction "PE15/CSI-D11/LCD-D15_16") (pintype "bidirectional"))
    )
    (net (code "136") (name "unconnected-(U1B-PE16{slash}CSI-D12{slash}LCD-D18-Pad15)") (class "Default")
      (node (ref "U1") (pin "15") (pinfunction "PE16/CSI-D12/LCD-D18_15") (pintype "bidirectional"))
    )
    (net (code "137") (name "unconnected-(U1B-PE17{slash}CSI-D13{slash}LCD-D19-Pad14)") (class "Default")
      (node (ref "U1") (pin "14") (pinfunction "PE17/CSI-D13/LCD-D19_14") (pintype "bidirectional"))
    )
    (net (code "138") (name "unconnected-(U1B-PE18{slash}CSI-D14{slash}LCD-D20-Pad13)") (class "Default")
      (node (ref "U1") (pin "13") (pinfunction "PE18/CSI-D14/LCD-D20_13") (pintype "bidirectional"))
    )
    (net (code "139") (name "unconnected-(U1B-PE19{slash}CSI-D15{slash}LCD-D21-Pad11)") (class "Default")
      (node (ref "U1") (pin "11") (pinfunction "PE19/CSI-D15/LCD-D21_11") (pintype "bidirectional"))
    )
    (net (code "140") (name "unconnected-(U1B-PE20{slash}CSI-FIELD{slash}CSI-MIPI-M-CLK-Pad10)") (class "Default")
      (node (ref "U1") (pin "10") (pinfunction "PE20/CSI-FIELD/CSI-MIPI-M-CLK_10") (pintype "bidirectional"))
    )
    (net (code "141") (name "unconnected-(U1B-PE23{slash}LCD-D22{slash}-Pad7)") (class "Default")
      (node (ref "U1") (pin "7") (pinfunction "PE23/LCD-D22/_7") (pintype "bidirectional"))
    )
    (net (code "142") (name "unconnected-(U1B-PE24{slash}LCD-D23-Pad6)") (class "Default")
      (node (ref "U1") (pin "6") (pinfunction "PE24/LCD-D23_6") (pintype "bidirectional"))
    )
    (net (code "143") (name "unconnected-(U1B-PF6-Pad100)") (class "Default")
      (node (ref "U1") (pin "100") (pinfunction "PF6_100") (pintype "bidirectional"))
    )
    (net (code "144") (name "unconnected-(U1B-PG3{slash}SDC1{slash}D1-Pad2)") (class "Default")
      (node (ref "U1") (pin "2") (pinfunction "PG3/SDC1/D1_2") (pintype "bidirectional"))
    )
    (net (code "145") (name "unconnected-(U1B-PG4{slash}SDC1{slash}D2-Pad1)") (class "Default")
      (node (ref "U1") (pin "1") (pinfunction "PG4/SDC1/D2_1") (pintype "bidirectional"))
    )
    (net (code "146") (name "unconnected-(U1B-PG5{slash}SDC1{slash}D3-Pad128)") (class "Default")
      (node (ref "U1") (pin "128") (pinfunction "PG5/SDC1/D3_128") (pintype "bidirectional"))
    )
    (net (code "147") (name "unconnected-(U1D-RESET-Pad99)") (class "Default")
      (node (ref "U1") (pin "99") (pinfunction "RESET_99") (pintype "bidirectional"))
    )
    (net (code "148") (name "unconnected-(U1E-EPHY_RTX-Pad94)") (class "Default")
      (node (ref "U1") (pin "94") (pinfunction "EPHY_RTX_94") (pintype "bidirectional"))
    )
    (net (code "149") (name "unconnected-(U1E-EPHY_RXN-Pad89)") (class "Default")
      (node (ref "U1") (pin "89") (pinfunction "EPHY_RXN_89") (pintype "bidirectional"))
    )
    (net (code "150") (name "unconnected-(U1E-EPHY_RXP-Pad90)") (class "Default")
      (node (ref "U1") (pin "90") (pinfunction "EPHY_RXP_90") (pintype "bidirectional"))
    )
    (net (code "151") (name "unconnected-(U1E-EPHY_TXN-Pad91)") (class "Default")
      (node (ref "U1") (pin "91") (pinfunction "EPHY_TXN_91") (pintype "bidirectional"))
    )
    (net (code "152") (name "unconnected-(U1E-EPHY_TXP-Pad92)") (class "Default")
      (node (ref "U1") (pin "92") (pinfunction "EPHY_TXP_92") (pintype "bidirectional"))
    )
    (net (code "153") (name "unconnected-(U6-BACKUP-Pad30)") (class "Default")
      (node (ref "U6") (pin "30") (pinfunction "BACKUP_30") (pintype "bidirectional"))
    )
    (net (code "154") (name "unconnected-(U6-DC3SET-Pad29)") (class "Default")
      (node (ref "U6") (pin "29") (pinfunction "DC3SET_29") (pintype "input"))
    )
    (net (code "155") (name "unconnected-(U6-EXTEN-Pad20)") (class "Default")
      (node (ref "U6") (pin "20") (pinfunction "EXTEN_20") (pintype "output"))
    )
    (net (code "156") (name "unconnected-(U6-GPIO0-Pad19)") (class "Default")
      (node (ref "U6") (pin "19") (pinfunction "GPIO0_19") (pintype "bidirectional"))
    )
    (net (code "157") (name "unconnected-(U6-GPIO1-Pad18)") (class "Default")
      (node (ref "U6") (pin "18") (pinfunction "GPIO1_18") (pintype "bidirectional"))
    )
    (net (code "158") (name "unconnected-(U6-GPIO2-Pad5)") (class "Default")
      (node (ref "U6") (pin "5") (pinfunction "GPIO2_5") (pintype "bidirectional"))
    )
    (net (code "159") (name "unconnected-(U6-GPIO3-Pad3)") (class "Default")
      (node (ref "U6") (pin "3") (pinfunction "GPIO3_3") (pintype "bidirectional"))
    )
  )
)
